# MN42_v2.net
KiCad netlist of a schematic drawn in EasyEDA Pro
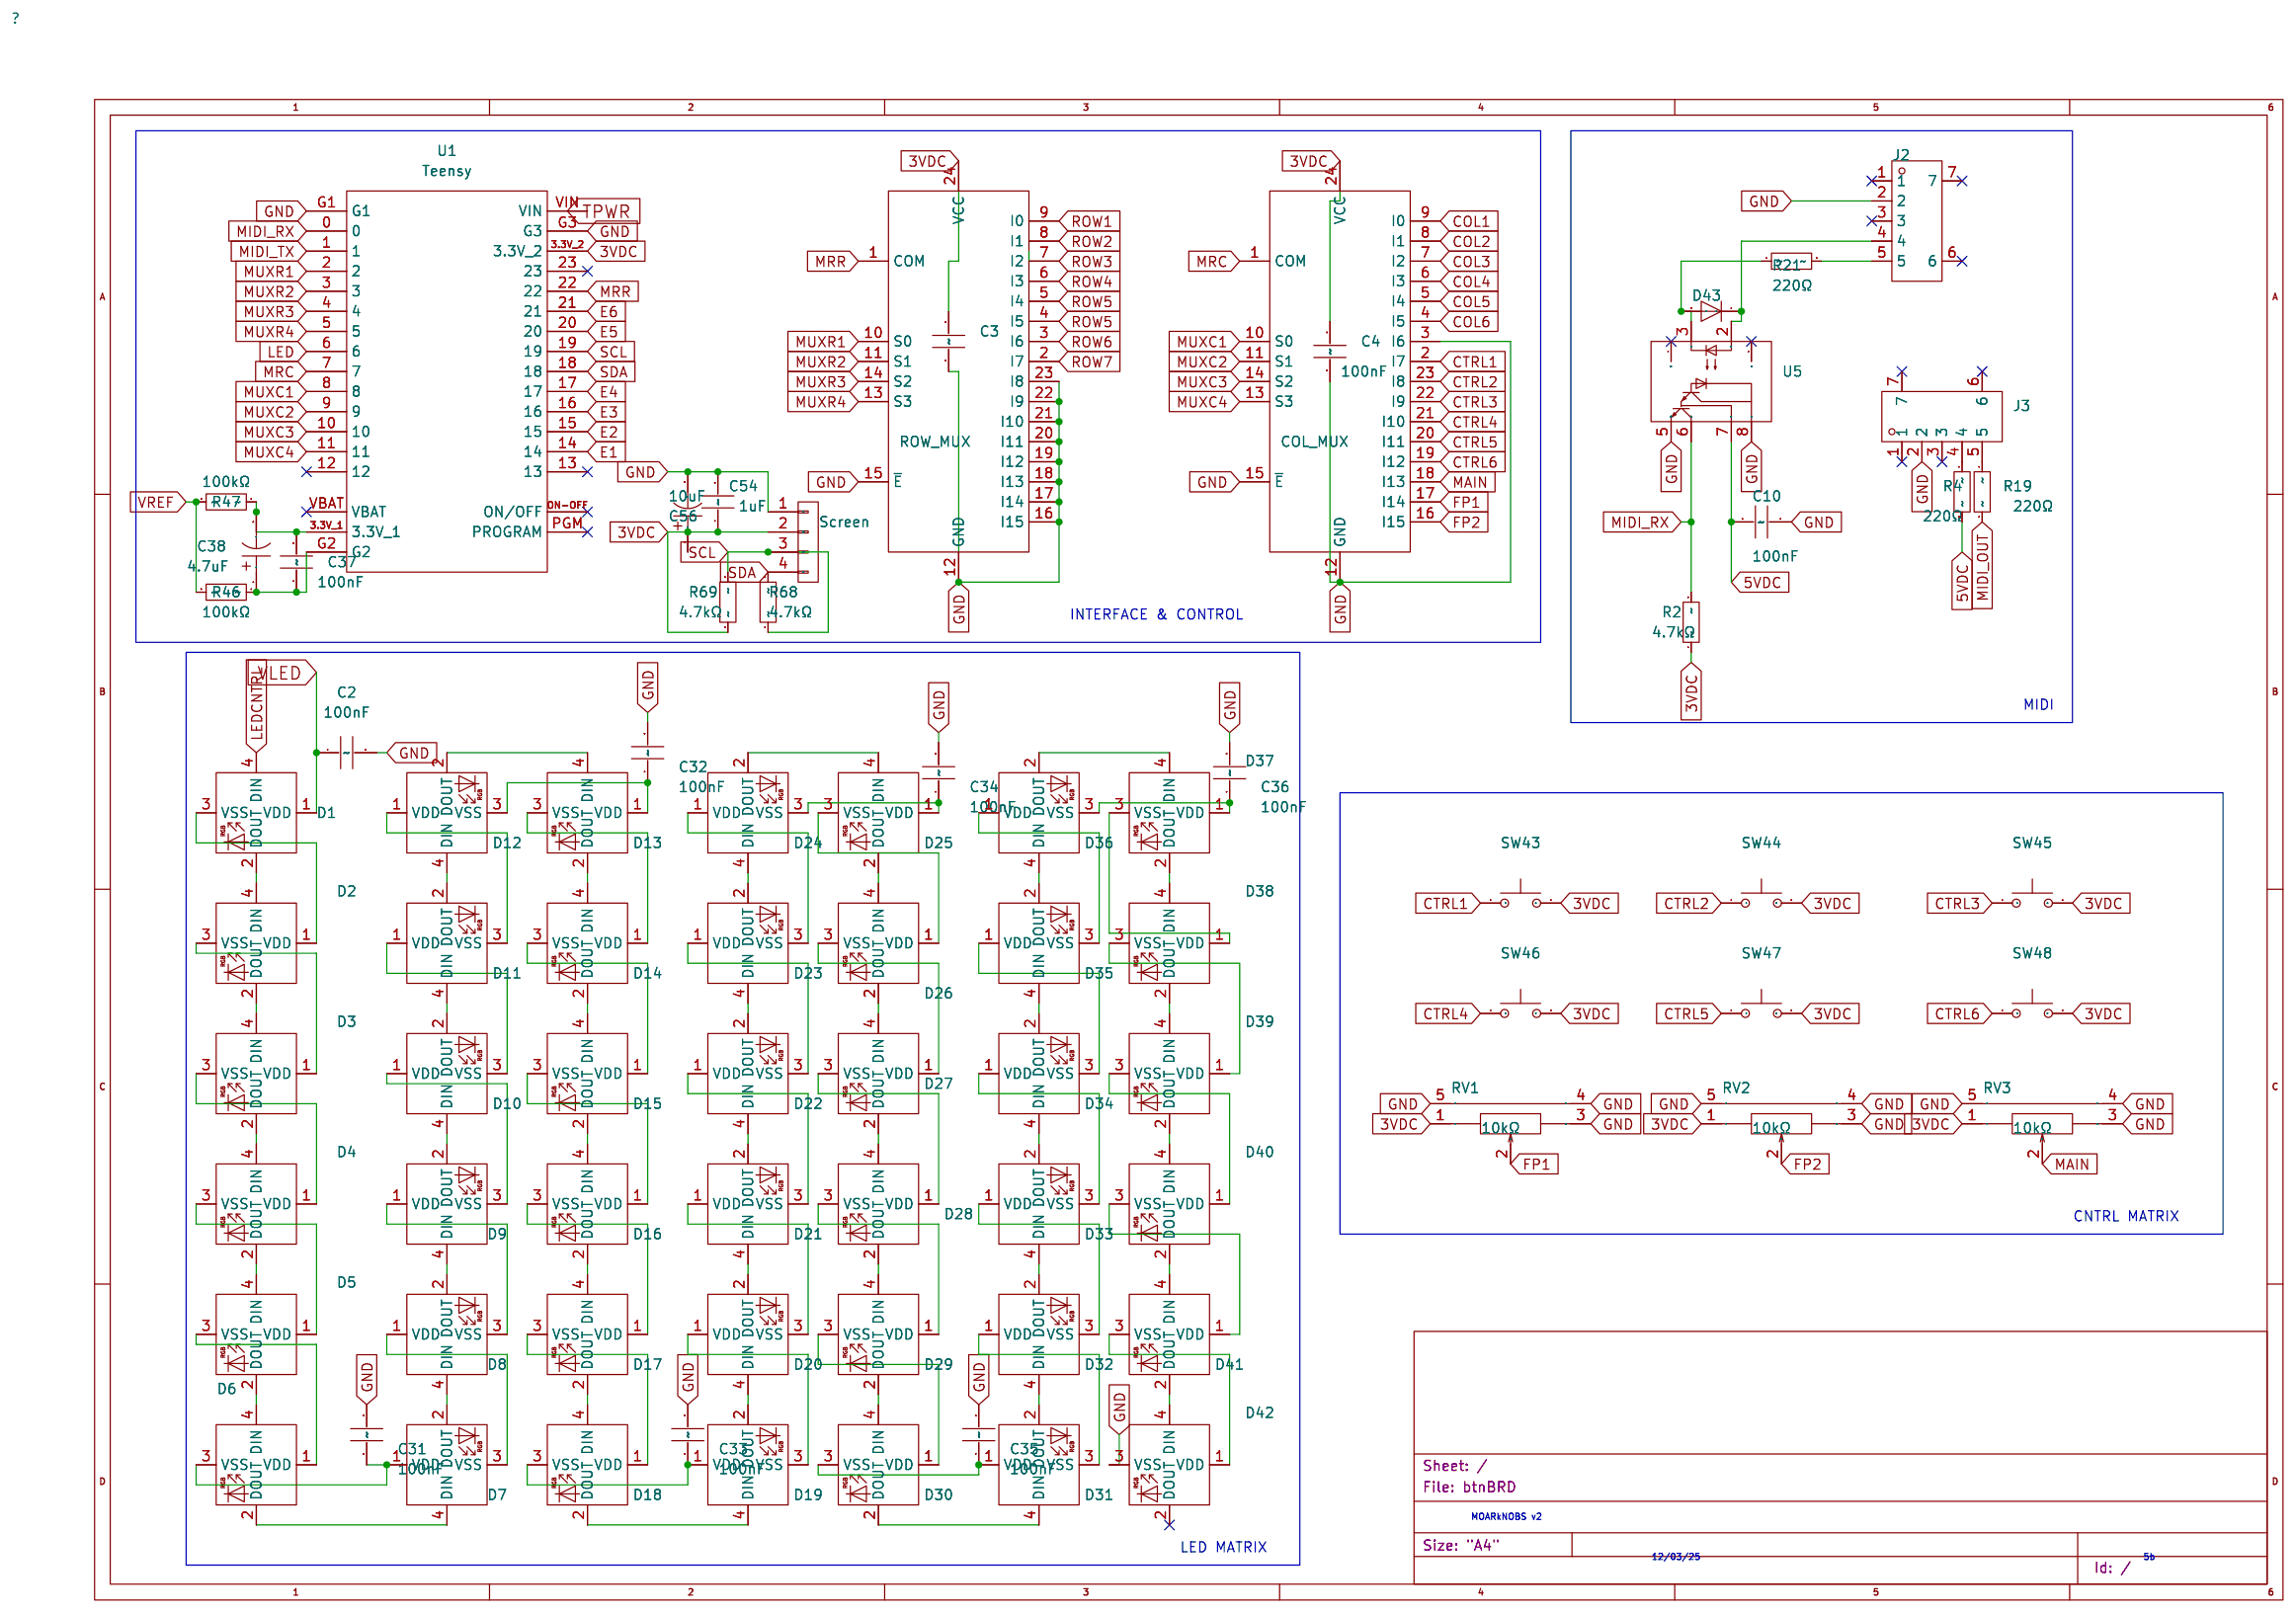
[diagram p0: btnBRD]
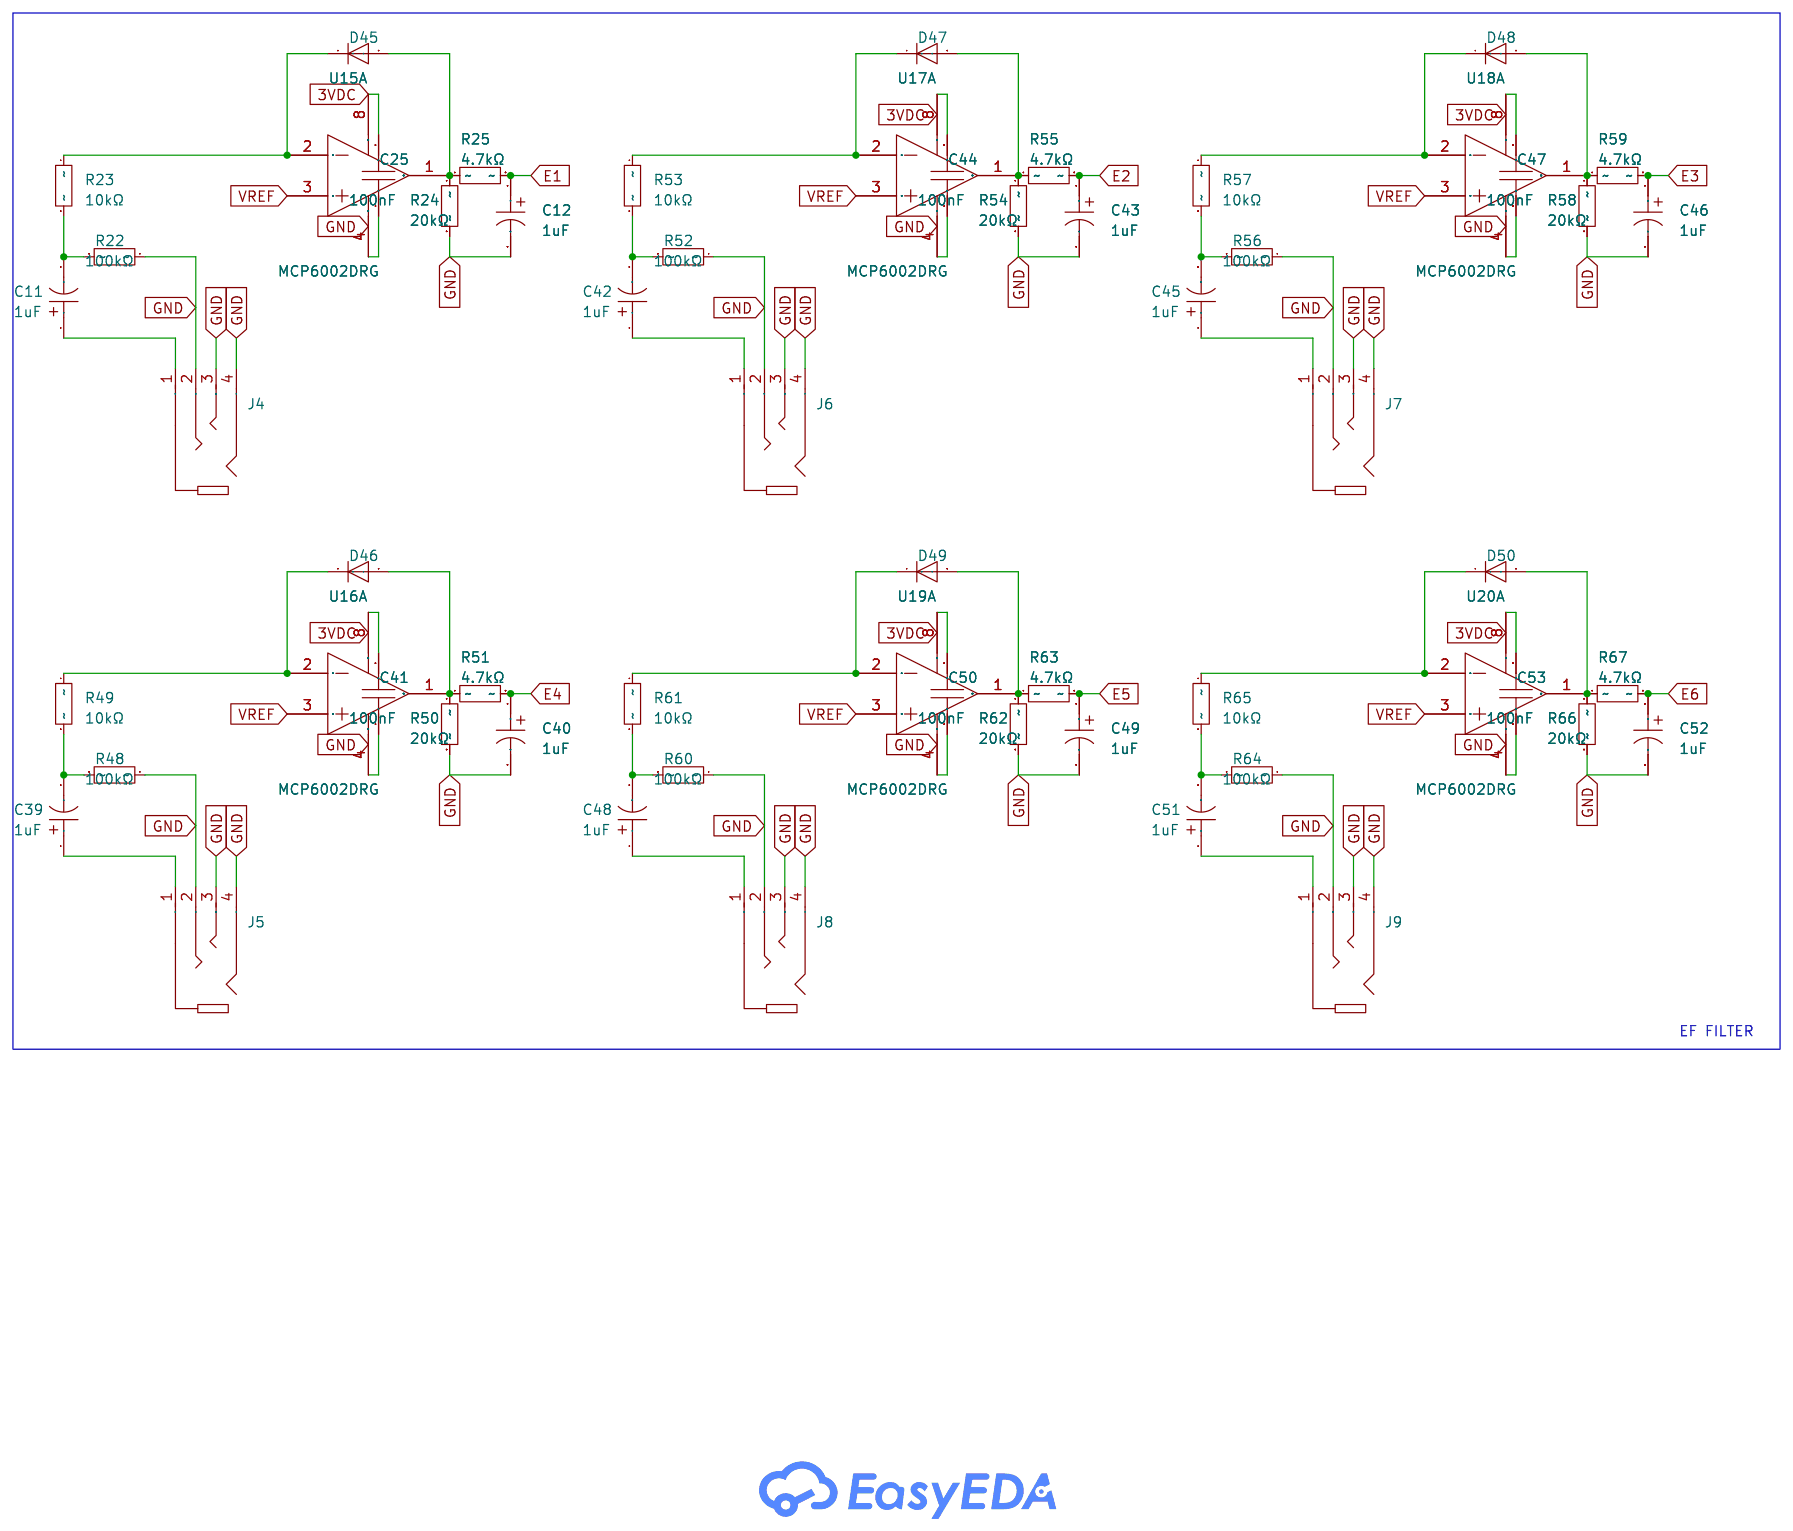
[diagram p1: P2]
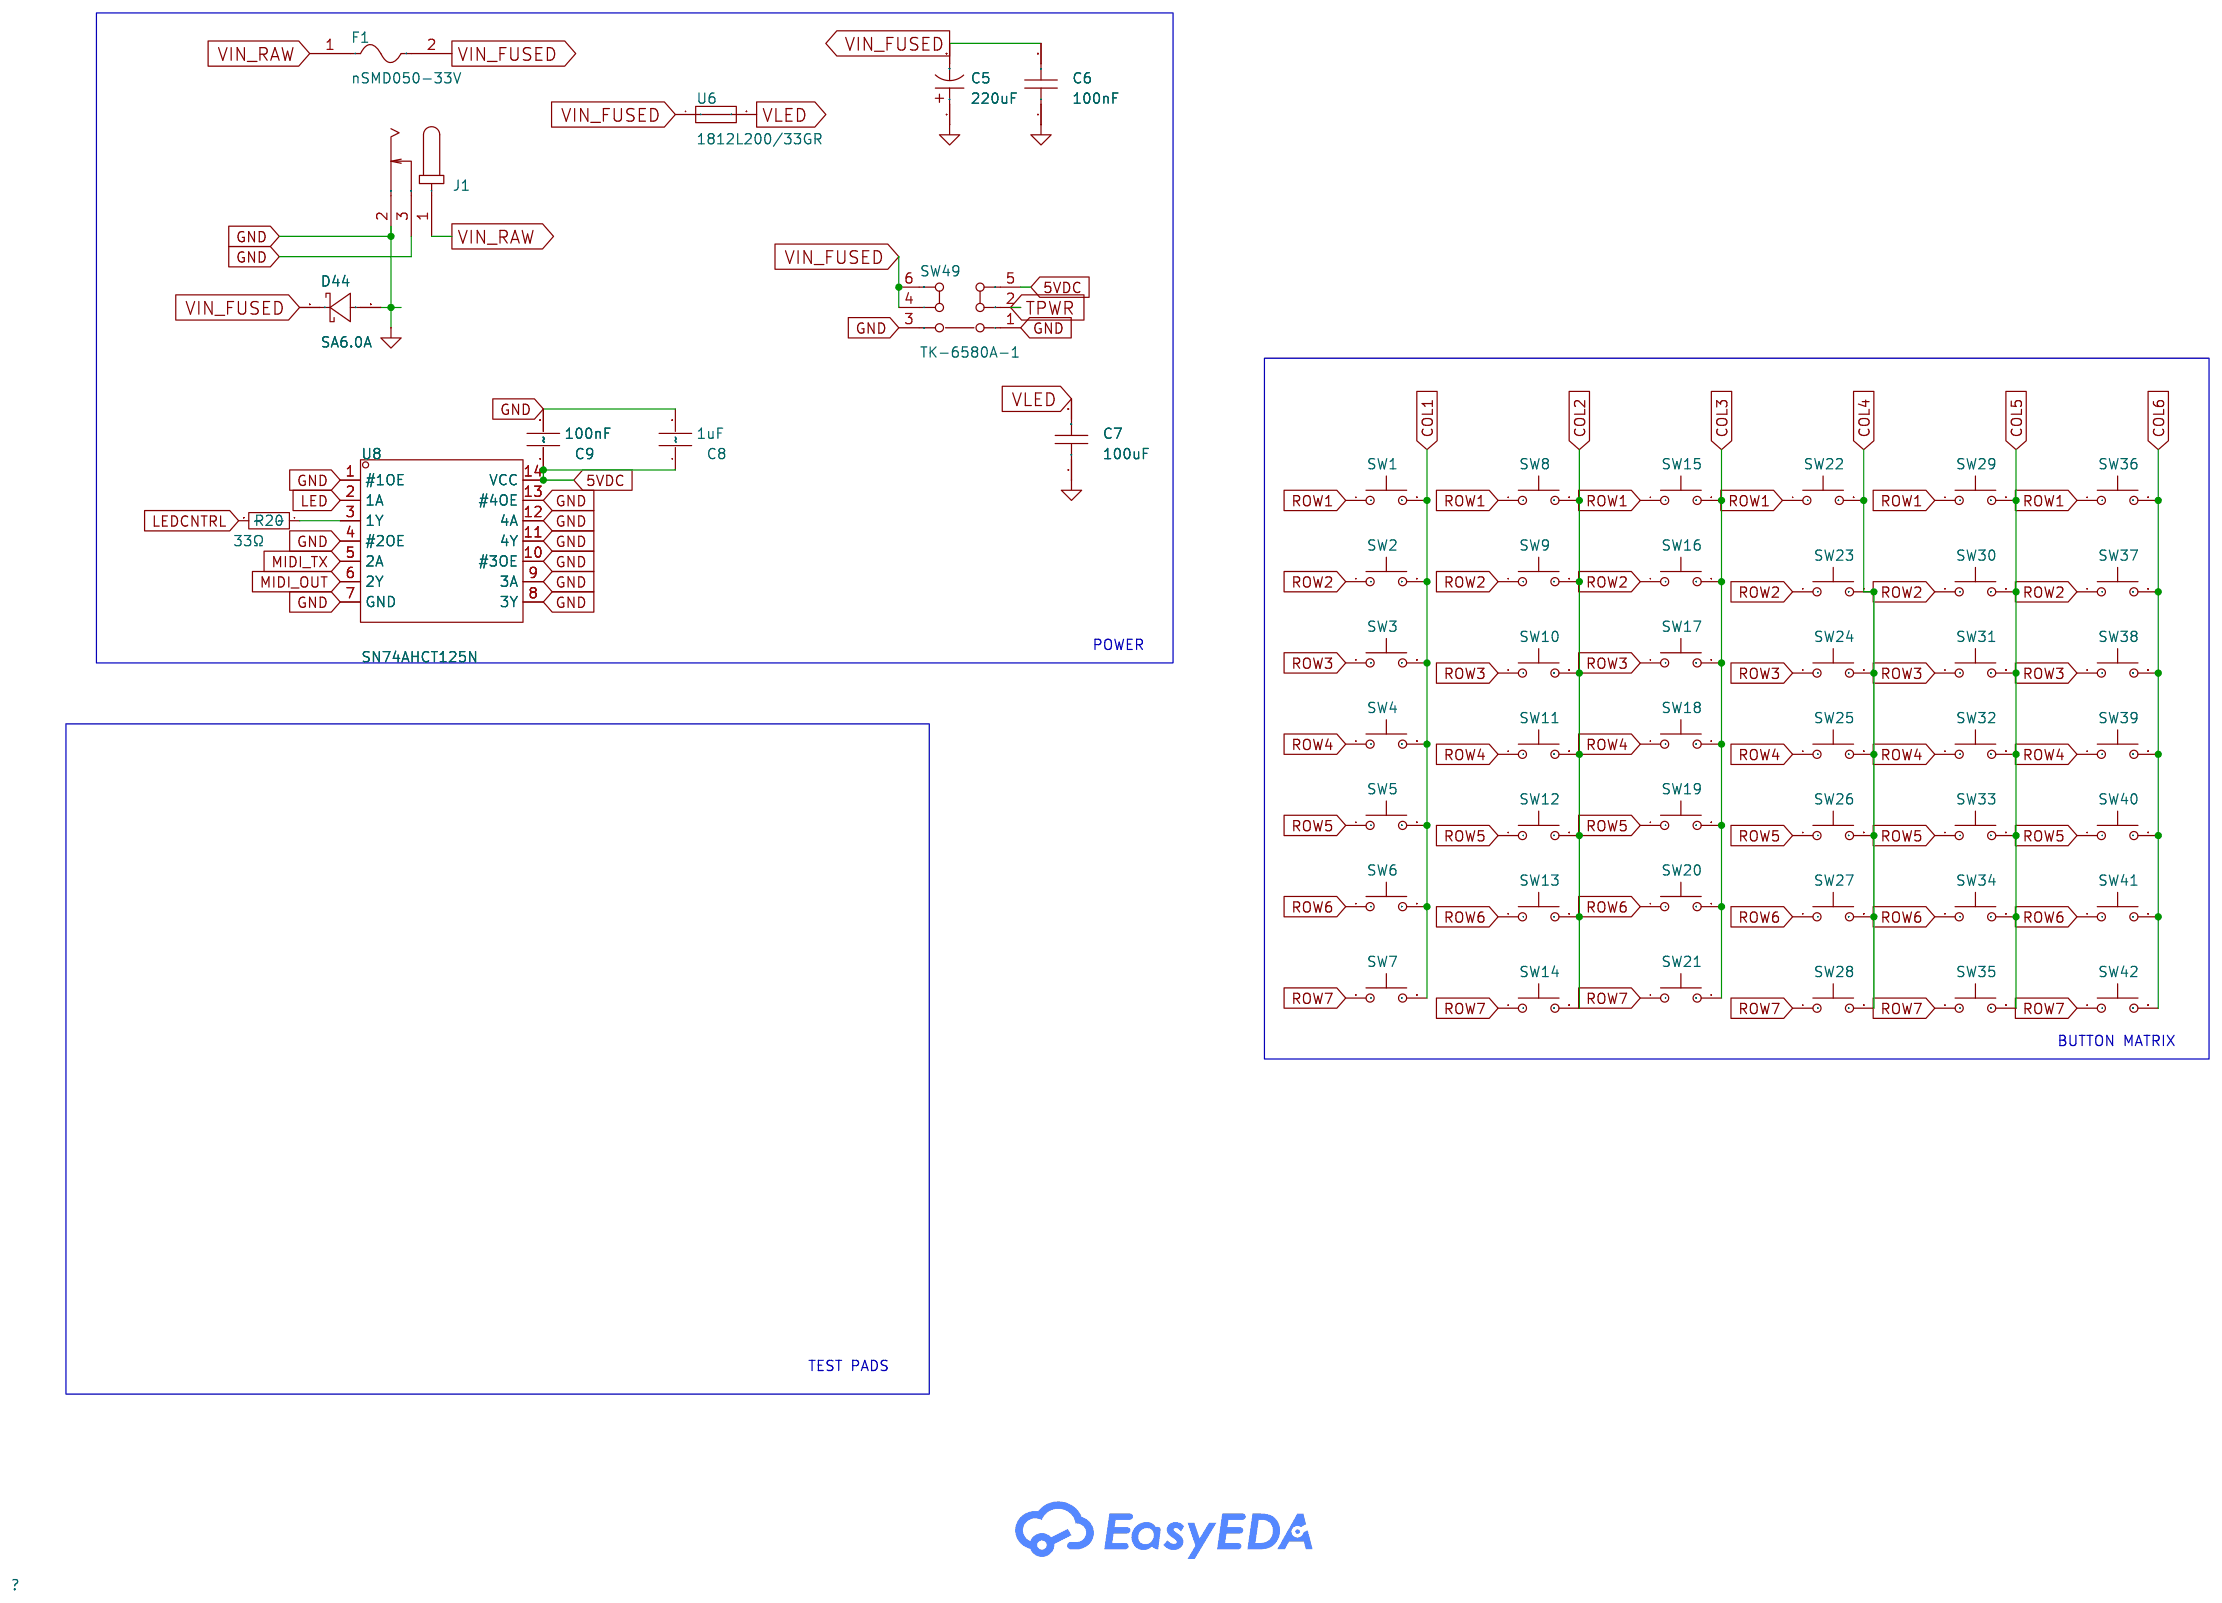
[diagram p2: P3]

(export (version "E")
  (design (tool "Eeschema 10.0.6"))
  (components
    (comp (ref "C2")
      (value "100nF")
      (footprint "easyedapro:Capacitor_THT:C_Disc_D3.4mm_W2.1mm_P2.50mm")
      (description "Capacitance:100nF Tolerance:±10% Tolerance:±10% Voltage Rating:63V Temperature Coefficient:-")
      (fields
        (field (name "Manufacturer Part") "CT4G-0805-2X1-63V-0.1μF-K")
        (field (name "Manufacturer") "TORCH(火炬)")
      )
      (libsource (lib "easyedapro") (part "Device_C"))
    )
    (comp (ref "C3")
      (value "100nF")
      (footprint "easyedapro:Capacitor_THT:C_Disc_D3.4mm_W2.1mm_P2.50mm")
      (description "Capacitance:100nF Tolerance:±10% Tolerance:±10% Voltage Rating:63V Temperature Coefficient:-")
      (fields
        (field (name "Manufacturer Part") "CT4G-0805-2X1-63V-0.1μF-K")
        (field (name "Manufacturer") "TORCH(火炬)")
      )
      (libsource (lib "easyedapro") (part "Device_C"))
    )
    (comp (ref "C4")
      (value "100nF")
      (footprint "easyedapro:Capacitor_THT:C_Disc_D3.4mm_W2.1mm_P2.50mm")
      (description "Capacitance:100nF Tolerance:±10% Tolerance:±10% Voltage Rating:63V Temperature Coefficient:-")
      (fields
        (field (name "Manufacturer Part") "CT4G-0805-2X1-63V-0.1μF-K")
        (field (name "Manufacturer") "TORCH(火炬)")
      )
      (libsource (lib "easyedapro") (part "Device_C"))
    )
    (comp (ref "C10")
      (value "100nF")
      (footprint "easyedapro:Capacitor_THT:C_Disc_D3.4mm_W2.1mm_P2.50mm")
      (description "Capacitance:100nF Tolerance:±10% Tolerance:±10% Voltage Rating:63V Temperature Coefficient:-")
      (fields
        (field (name "Manufacturer Part") "CT4G-0805-2X1-63V-0.1μF-K")
        (field (name "Manufacturer") "TORCH(火炬)")
      )
      (libsource (lib "easyedapro") (part "Device_C"))
    )
    (comp (ref "C31")
      (value "100nF")
      (footprint "easyedapro:Capacitor_THT:C_Disc_D3.4mm_W2.1mm_P2.50mm")
      (description "Capacitance:100nF Tolerance:±10% Tolerance:±10% Voltage Rating:63V Temperature Coefficient:-")
      (fields
        (field (name "Manufacturer Part") "CT4G-0805-2X1-63V-0.1μF-K")
        (field (name "Manufacturer") "TORCH(火炬)")
      )
      (libsource (lib "easyedapro") (part "Device_C"))
    )
    (comp (ref "C32")
      (value "100nF")
      (footprint "easyedapro:Capacitor_THT:C_Disc_D3.4mm_W2.1mm_P2.50mm")
      (description "Capacitance:100nF Tolerance:±10% Tolerance:±10% Voltage Rating:63V Temperature Coefficient:-")
      (fields
        (field (name "Manufacturer Part") "CT4G-0805-2X1-63V-0.1μF-K")
        (field (name "Manufacturer") "TORCH(火炬)")
      )
      (libsource (lib "easyedapro") (part "Device_C"))
    )
    (comp (ref "C33")
      (value "100nF")
      (footprint "easyedapro:Capacitor_THT:C_Disc_D3.4mm_W2.1mm_P2.50mm")
      (description "Capacitance:100nF Tolerance:±10% Tolerance:±10% Voltage Rating:63V Temperature Coefficient:-")
      (fields
        (field (name "Manufacturer Part") "CT4G-0805-2X1-63V-0.1μF-K")
        (field (name "Manufacturer") "TORCH(火炬)")
      )
      (libsource (lib "easyedapro") (part "Device_C"))
    )
    (comp (ref "C34")
      (value "100nF")
      (footprint "easyedapro:Capacitor_THT:C_Disc_D3.4mm_W2.1mm_P2.50mm")
      (description "Capacitance:100nF Tolerance:±10% Tolerance:±10% Voltage Rating:63V Temperature Coefficient:-")
      (fields
        (field (name "Manufacturer Part") "CT4G-0805-2X1-63V-0.1μF-K")
        (field (name "Manufacturer") "TORCH(火炬)")
      )
      (libsource (lib "easyedapro") (part "Device_C"))
    )
    (comp (ref "C35")
      (value "100nF")
      (footprint "easyedapro:Capacitor_THT:C_Disc_D3.4mm_W2.1mm_P2.50mm")
      (description "Capacitance:100nF Tolerance:±10% Tolerance:±10% Voltage Rating:63V Temperature Coefficient:-")
      (fields
        (field (name "Manufacturer Part") "CT4G-0805-2X1-63V-0.1μF-K")
        (field (name "Manufacturer") "TORCH(火炬)")
      )
      (libsource (lib "easyedapro") (part "Device_C"))
    )
    (comp (ref "C36")
      (value "100nF")
      (footprint "easyedapro:Capacitor_THT:C_Disc_D3.4mm_W2.1mm_P2.50mm")
      (description "Capacitance:100nF Tolerance:±10% Tolerance:±10% Voltage Rating:63V Temperature Coefficient:-")
      (fields
        (field (name "Manufacturer Part") "CT4G-0805-2X1-63V-0.1μF-K")
        (field (name "Manufacturer") "TORCH(火炬)")
      )
      (libsource (lib "easyedapro") (part "Device_C"))
    )
    (comp (ref "C37")
      (value "100nF")
      (footprint "easyedapro:Capacitor_THT:C_Disc_D3.4mm_W2.1mm_P2.50mm")
      (description "Capacitance:100nF Tolerance:±10% Tolerance:±10% Voltage Rating:63V Temperature Coefficient:-")
      (fields
        (field (name "Manufacturer Part") "CT4G-0805-2X1-63V-0.1μF-K")
        (field (name "Manufacturer") "TORCH(火炬)")
      )
      (libsource (lib "easyedapro") (part "Device_C"))
    )
    (comp (ref "C38")
      (value "4.7uF")
      (footprint "easyedapro:CAP-SMD_BD6.3-L6.6-W6.6-FD")
      (fields (field (name "Manufacturer Part") "189RV0019") (field (name "Manufacturer") "KNSCHA(科尼盛)"))
      (libsource (lib "easyedapro") (part "189RV0019"))
    )
    (comp (ref "C54")
      (value "1uF")
      (footprint "easyedapro:Capacitor_THT:C_Disc_D3.4mm_W2.1mm_P2.50mm")
      (description "Capacitance:100nF Tolerance:±10% Tolerance:±10% Voltage Rating:63V Temperature Coefficient:-")
      (fields
        (field (name "Manufacturer Part") "CT4G-0805-2X1-63V-0.1μF-K")
        (field (name "Manufacturer") "TORCH(火炬)")
      )
      (libsource (lib "easyedapro") (part "Device_C"))
    )
    (comp (ref "C56")
      (value "10uF")
      (footprint "easyedapro:CAP-SMD_BD6.3-L6.6-W6.6-FD")
      (fields (field (name "Manufacturer Part") "189RV0019") (field (name "Manufacturer") "KNSCHA(科尼盛)"))
      (libsource (lib "easyedapro") (part "189RV0019"))
    )
    (comp (ref "COL_MUX")
      (value "CD74HC4067M96")
      (footprint "easyedapro:Package_SO:SOIC-24W_7.5x15.4mm_P1.27mm")
      (fields (field (name "Manufacturer") "TI(德州仪器)"))
      (libsource (lib "easyedapro") (part "74xx_CD74HC4067M"))
    )
    (comp (ref "D1")
      (value "XL-5050RGBC-WS2812B")
      (footprint "easyedapro:LED_SMD:LED_WS2812B_PLCC4_5.0x5.0mm_P3.2mm")
      (fields (field (name "Manufacturer") "XINGLIGHT(成兴光)"))
      (libsource (lib "easyedapro") (part "LED_WS2812B"))
    )
    (comp (ref "D2")
      (value "XL-5050RGBC-WS2812B")
      (footprint "easyedapro:LED_SMD:LED_WS2812B_PLCC4_5.0x5.0mm_P3.2mm")
      (fields (field (name "Manufacturer") "XINGLIGHT(成兴光)"))
      (libsource (lib "easyedapro") (part "LED_WS2812B"))
    )
    (comp (ref "D3")
      (value "XL-5050RGBC-WS2812B")
      (footprint "easyedapro:LED_SMD:LED_WS2812B_PLCC4_5.0x5.0mm_P3.2mm")
      (fields (field (name "Manufacturer") "XINGLIGHT(成兴光)"))
      (libsource (lib "easyedapro") (part "LED_WS2812B"))
    )
    (comp (ref "D4")
      (value "XL-5050RGBC-WS2812B")
      (footprint "easyedapro:LED_SMD:LED_WS2812B_PLCC4_5.0x5.0mm_P3.2mm")
      (fields (field (name "Manufacturer") "XINGLIGHT(成兴光)"))
      (libsource (lib "easyedapro") (part "LED_WS2812B"))
    )
    (comp (ref "D5")
      (value "XL-5050RGBC-WS2812B")
      (footprint "easyedapro:LED_SMD:LED_WS2812B_PLCC4_5.0x5.0mm_P3.2mm")
      (fields (field (name "Manufacturer") "XINGLIGHT(成兴光)"))
      (libsource (lib "easyedapro") (part "LED_WS2812B"))
    )
    (comp (ref "D6")
      (value "XL-5050RGBC-WS2812B")
      (footprint "easyedapro:LED_SMD:LED_WS2812B_PLCC4_5.0x5.0mm_P3.2mm")
      (fields (field (name "Manufacturer") "XINGLIGHT(成兴光)"))
      (libsource (lib "easyedapro") (part "LED_WS2812B"))
    )
    (comp (ref "D7")
      (value "XL-5050RGBC-WS2812B")
      (footprint "easyedapro:LED_SMD:LED_WS2812B_PLCC4_5.0x5.0mm_P3.2mm")
      (fields (field (name "Manufacturer") "XINGLIGHT(成兴光)"))
      (libsource (lib "easyedapro") (part "LED_WS2812B"))
    )
    (comp (ref "D8")
      (value "XL-5050RGBC-WS2812B")
      (footprint "easyedapro:LED_SMD:LED_WS2812B_PLCC4_5.0x5.0mm_P3.2mm")
      (fields (field (name "Manufacturer") "XINGLIGHT(成兴光)"))
      (libsource (lib "easyedapro") (part "LED_WS2812B"))
    )
    (comp (ref "D9")
      (value "XL-5050RGBC-WS2812B")
      (footprint "easyedapro:LED_SMD:LED_WS2812B_PLCC4_5.0x5.0mm_P3.2mm")
      (fields (field (name "Manufacturer") "XINGLIGHT(成兴光)"))
      (libsource (lib "easyedapro") (part "LED_WS2812B"))
    )
    (comp (ref "D10")
      (value "XL-5050RGBC-WS2812B")
      (footprint "easyedapro:LED_SMD:LED_WS2812B_PLCC4_5.0x5.0mm_P3.2mm")
      (fields (field (name "Manufacturer") "XINGLIGHT(成兴光)"))
      (libsource (lib "easyedapro") (part "LED_WS2812B"))
    )
    (comp (ref "D11")
      (value "XL-5050RGBC-WS2812B")
      (footprint "easyedapro:LED_SMD:LED_WS2812B_PLCC4_5.0x5.0mm_P3.2mm")
      (fields (field (name "Manufacturer") "XINGLIGHT(成兴光)"))
      (libsource (lib "easyedapro") (part "LED_WS2812B"))
    )
    (comp (ref "D12")
      (value "XL-5050RGBC-WS2812B")
      (footprint "easyedapro:LED_SMD:LED_WS2812B_PLCC4_5.0x5.0mm_P3.2mm")
      (fields (field (name "Manufacturer") "XINGLIGHT(成兴光)"))
      (libsource (lib "easyedapro") (part "LED_WS2812B"))
    )
    (comp (ref "D13")
      (value "XL-5050RGBC-WS2812B")
      (footprint "easyedapro:LED_SMD:LED_WS2812B_PLCC4_5.0x5.0mm_P3.2mm")
      (fields (field (name "Manufacturer") "XINGLIGHT(成兴光)"))
      (libsource (lib "easyedapro") (part "LED_WS2812B"))
    )
    (comp (ref "D14")
      (value "XL-5050RGBC-WS2812B")
      (footprint "easyedapro:LED_SMD:LED_WS2812B_PLCC4_5.0x5.0mm_P3.2mm")
      (fields (field (name "Manufacturer") "XINGLIGHT(成兴光)"))
      (libsource (lib "easyedapro") (part "LED_WS2812B"))
    )
    (comp (ref "D15")
      (value "XL-5050RGBC-WS2812B")
      (footprint "easyedapro:LED_SMD:LED_WS2812B_PLCC4_5.0x5.0mm_P3.2mm")
      (fields (field (name "Manufacturer") "XINGLIGHT(成兴光)"))
      (libsource (lib "easyedapro") (part "LED_WS2812B"))
    )
    (comp (ref "D16")
      (value "XL-5050RGBC-WS2812B")
      (footprint "easyedapro:LED_SMD:LED_WS2812B_PLCC4_5.0x5.0mm_P3.2mm")
      (fields (field (name "Manufacturer") "XINGLIGHT(成兴光)"))
      (libsource (lib "easyedapro") (part "LED_WS2812B"))
    )
    (comp (ref "D17")
      (value "XL-5050RGBC-WS2812B")
      (footprint "easyedapro:LED_SMD:LED_WS2812B_PLCC4_5.0x5.0mm_P3.2mm")
      (fields (field (name "Manufacturer") "XINGLIGHT(成兴光)"))
      (libsource (lib "easyedapro") (part "LED_WS2812B"))
    )
    (comp (ref "D18")
      (value "XL-5050RGBC-WS2812B")
      (footprint "easyedapro:LED_SMD:LED_WS2812B_PLCC4_5.0x5.0mm_P3.2mm")
      (fields (field (name "Manufacturer") "XINGLIGHT(成兴光)"))
      (libsource (lib "easyedapro") (part "LED_WS2812B"))
    )
    (comp (ref "D19")
      (value "XL-5050RGBC-WS2812B")
      (footprint "easyedapro:LED_SMD:LED_WS2812B_PLCC4_5.0x5.0mm_P3.2mm")
      (fields (field (name "Manufacturer") "XINGLIGHT(成兴光)"))
      (libsource (lib "easyedapro") (part "LED_WS2812B"))
    )
    (comp (ref "D20")
      (value "XL-5050RGBC-WS2812B")
      (footprint "easyedapro:LED_SMD:LED_WS2812B_PLCC4_5.0x5.0mm_P3.2mm")
      (fields (field (name "Manufacturer") "XINGLIGHT(成兴光)"))
      (libsource (lib "easyedapro") (part "LED_WS2812B"))
    )
    (comp (ref "D21")
      (value "XL-5050RGBC-WS2812B")
      (footprint "easyedapro:LED_SMD:LED_WS2812B_PLCC4_5.0x5.0mm_P3.2mm")
      (fields (field (name "Manufacturer") "XINGLIGHT(成兴光)"))
      (libsource (lib "easyedapro") (part "LED_WS2812B"))
    )
    (comp (ref "D22")
      (value "XL-5050RGBC-WS2812B")
      (footprint "easyedapro:LED_SMD:LED_WS2812B_PLCC4_5.0x5.0mm_P3.2mm")
      (fields (field (name "Manufacturer") "XINGLIGHT(成兴光)"))
      (libsource (lib "easyedapro") (part "LED_WS2812B"))
    )
    (comp (ref "D23")
      (value "XL-5050RGBC-WS2812B")
      (footprint "easyedapro:LED_SMD:LED_WS2812B_PLCC4_5.0x5.0mm_P3.2mm")
      (fields (field (name "Manufacturer") "XINGLIGHT(成兴光)"))
      (libsource (lib "easyedapro") (part "LED_WS2812B"))
    )
    (comp (ref "D24")
      (value "XL-5050RGBC-WS2812B")
      (footprint "easyedapro:LED_SMD:LED_WS2812B_PLCC4_5.0x5.0mm_P3.2mm")
      (fields (field (name "Manufacturer") "XINGLIGHT(成兴光)"))
      (libsource (lib "easyedapro") (part "LED_WS2812B"))
    )
    (comp (ref "D25")
      (value "XL-5050RGBC-WS2812B")
      (footprint "easyedapro:LED_SMD:LED_WS2812B_PLCC4_5.0x5.0mm_P3.2mm")
      (fields (field (name "Manufacturer") "XINGLIGHT(成兴光)"))
      (libsource (lib "easyedapro") (part "LED_WS2812B"))
    )
    (comp (ref "D26")
      (value "XL-5050RGBC-WS2812B")
      (footprint "easyedapro:LED_SMD:LED_WS2812B_PLCC4_5.0x5.0mm_P3.2mm")
      (fields (field (name "Manufacturer") "XINGLIGHT(成兴光)"))
      (libsource (lib "easyedapro") (part "LED_WS2812B"))
    )
    (comp (ref "D27")
      (value "XL-5050RGBC-WS2812B")
      (footprint "easyedapro:LED_SMD:LED_WS2812B_PLCC4_5.0x5.0mm_P3.2mm")
      (fields (field (name "Manufacturer") "XINGLIGHT(成兴光)"))
      (libsource (lib "easyedapro") (part "LED_WS2812B"))
    )
    (comp (ref "D28")
      (value "XL-5050RGBC-WS2812B")
      (footprint "easyedapro:LED_SMD:LED_WS2812B_PLCC4_5.0x5.0mm_P3.2mm")
      (fields (field (name "Manufacturer") "XINGLIGHT(成兴光)"))
      (libsource (lib "easyedapro") (part "LED_WS2812B"))
    )
    (comp (ref "D29")
      (value "XL-5050RGBC-WS2812B")
      (footprint "easyedapro:LED_SMD:LED_WS2812B_PLCC4_5.0x5.0mm_P3.2mm")
      (fields (field (name "Manufacturer") "XINGLIGHT(成兴光)"))
      (libsource (lib "easyedapro") (part "LED_WS2812B"))
    )
    (comp (ref "D30")
      (value "XL-5050RGBC-WS2812B")
      (footprint "easyedapro:LED_SMD:LED_WS2812B_PLCC4_5.0x5.0mm_P3.2mm")
      (fields (field (name "Manufacturer") "XINGLIGHT(成兴光)"))
      (libsource (lib "easyedapro") (part "LED_WS2812B"))
    )
    (comp (ref "D31")
      (value "XL-5050RGBC-WS2812B")
      (footprint "easyedapro:LED_SMD:LED_WS2812B_PLCC4_5.0x5.0mm_P3.2mm")
      (fields (field (name "Manufacturer") "XINGLIGHT(成兴光)"))
      (libsource (lib "easyedapro") (part "LED_WS2812B"))
    )
    (comp (ref "D32")
      (value "XL-5050RGBC-WS2812B")
      (footprint "easyedapro:LED_SMD:LED_WS2812B_PLCC4_5.0x5.0mm_P3.2mm")
      (fields (field (name "Manufacturer") "XINGLIGHT(成兴光)"))
      (libsource (lib "easyedapro") (part "LED_WS2812B"))
    )
    (comp (ref "D33")
      (value "XL-5050RGBC-WS2812B")
      (footprint "easyedapro:LED_SMD:LED_WS2812B_PLCC4_5.0x5.0mm_P3.2mm")
      (fields (field (name "Manufacturer") "XINGLIGHT(成兴光)"))
      (libsource (lib "easyedapro") (part "LED_WS2812B"))
    )
    (comp (ref "D34")
      (value "XL-5050RGBC-WS2812B")
      (footprint "easyedapro:LED_SMD:LED_WS2812B_PLCC4_5.0x5.0mm_P3.2mm")
      (fields (field (name "Manufacturer") "XINGLIGHT(成兴光)"))
      (libsource (lib "easyedapro") (part "LED_WS2812B"))
    )
    (comp (ref "D35")
      (value "XL-5050RGBC-WS2812B")
      (footprint "easyedapro:LED_SMD:LED_WS2812B_PLCC4_5.0x5.0mm_P3.2mm")
      (fields (field (name "Manufacturer") "XINGLIGHT(成兴光)"))
      (libsource (lib "easyedapro") (part "LED_WS2812B"))
    )
    (comp (ref "D36")
      (value "XL-5050RGBC-WS2812B")
      (footprint "easyedapro:LED_SMD:LED_WS2812B_PLCC4_5.0x5.0mm_P3.2mm")
      (fields (field (name "Manufacturer") "XINGLIGHT(成兴光)"))
      (libsource (lib "easyedapro") (part "LED_WS2812B"))
    )
    (comp (ref "D37")
      (value "XL-5050RGBC-WS2812B")
      (footprint "easyedapro:LED_SMD:LED_WS2812B_PLCC4_5.0x5.0mm_P3.2mm")
      (fields (field (name "Manufacturer") "XINGLIGHT(成兴光)"))
      (libsource (lib "easyedapro") (part "LED_WS2812B"))
    )
    (comp (ref "D38")
      (value "XL-5050RGBC-WS2812B")
      (footprint "easyedapro:LED_SMD:LED_WS2812B_PLCC4_5.0x5.0mm_P3.2mm")
      (fields (field (name "Manufacturer") "XINGLIGHT(成兴光)"))
      (libsource (lib "easyedapro") (part "LED_WS2812B"))
    )
    (comp (ref "D39")
      (value "XL-5050RGBC-WS2812B")
      (footprint "easyedapro:LED_SMD:LED_WS2812B_PLCC4_5.0x5.0mm_P3.2mm")
      (fields (field (name "Manufacturer") "XINGLIGHT(成兴光)"))
      (libsource (lib "easyedapro") (part "LED_WS2812B"))
    )
    (comp (ref "D40")
      (value "XL-5050RGBC-WS2812B")
      (footprint "easyedapro:LED_SMD:LED_WS2812B_PLCC4_5.0x5.0mm_P3.2mm")
      (fields (field (name "Manufacturer") "XINGLIGHT(成兴光)"))
      (libsource (lib "easyedapro") (part "LED_WS2812B"))
    )
    (comp (ref "D41")
      (value "XL-5050RGBC-WS2812B")
      (footprint "easyedapro:LED_SMD:LED_WS2812B_PLCC4_5.0x5.0mm_P3.2mm")
      (fields (field (name "Manufacturer") "XINGLIGHT(成兴光)"))
      (libsource (lib "easyedapro") (part "LED_WS2812B"))
    )
    (comp (ref "D42")
      (value "XL-5050RGBC-WS2812B")
      (footprint "easyedapro:LED_SMD:LED_WS2812B_PLCC4_5.0x5.0mm_P3.2mm")
      (fields (field (name "Manufacturer") "XINGLIGHT(成兴光)"))
      (libsource (lib "easyedapro") (part "LED_WS2812B"))
    )
    (comp (ref "D43")
      (value "1N4148PF")
      (footprint "easyedapro:Diode_THT:D_DO-35_SOD27_P7.62mm_Horizontal")
      (fields (field (name "Manufacturer") "ST(先科)"))
      (libsource (lib "easyedapro") (part "Diode_1N4148"))
    )
    (comp (ref "J2")
      (value "DIN-504B-M10")
      (footprint "easyedapro:CONN-TH_DIN-504B-M10")
      (fields (field (name "Manufacturer") "HOOYA(皓宇电子)"))
      (libsource (lib "easyedapro") (part "DIN-504B-M10"))
    )
    (comp (ref "J3")
      (value "DIN-504B-M10")
      (footprint "easyedapro:CONN-TH_DIN-504B-M10")
      (fields (field (name "Manufacturer") "HOOYA(皓宇电子)"))
      (libsource (lib "easyedapro") (part "DIN-504B-M10"))
    )
    (comp (ref "R2")
      (value "4.7kΩ")
      (footprint "easyedapro:Resistor_THT:R_Axial_DIN0204_L3.6mm_D1.6mm_P2.54mm_Vertical")
      (fields
        (field (name "Manufacturer Part") "RN 1/8W 4K7 F T/B A1")
        (field (name "Manufacturer") "Tyohm(幸亚电阻)")
      )
      (libsource (lib "easyedapro") (part "Device_R"))
    )
    (comp (ref "R4")
      (value "220Ω")
      (footprint "easyedapro:Resistor_THT:R_Axial_DIN0204_L3.6mm_D1.6mm_P2.54mm_Vertical")
      (fields
        (field (name "Manufacturer Part") "RN 1/8W 220R F T/B A1")
        (field (name "Manufacturer") "Tyohm(幸亚电阻)")
      )
      (libsource (lib "easyedapro") (part "Device_R"))
    )
    (comp (ref "R19")
      (value "220Ω")
      (footprint "easyedapro:Resistor_THT:R_Axial_DIN0204_L3.6mm_D1.6mm_P2.54mm_Vertical")
      (fields
        (field (name "Manufacturer Part") "RN 1/8W 220R F T/B A1")
        (field (name "Manufacturer") "Tyohm(幸亚电阻)")
      )
      (libsource (lib "easyedapro") (part "Device_R"))
    )
    (comp (ref "R21")
      (value "220Ω")
      (footprint "easyedapro:Resistor_THT:R_Axial_DIN0204_L3.6mm_D1.6mm_P2.54mm_Vertical")
      (fields
        (field (name "Manufacturer Part") "RN 1/8W 220R F T/B A1")
        (field (name "Manufacturer") "Tyohm(幸亚电阻)")
      )
      (libsource (lib "easyedapro") (part "Device_R"))
    )
    (comp (ref "R46")
      (value "100kΩ")
      (footprint "easyedapro:Resistor_THT:R_Axial_DIN0204_L3.6mm_D1.6mm_P2.54mm_Vertical")
      (fields
        (field (name "Manufacturer Part") "RN1/8W10KFT/BA1")
        (field (name "Manufacturer") "Tyohm(幸亚电阻)")
      )
      (libsource (lib "easyedapro") (part "Device_R"))
    )
    (comp (ref "R47")
      (value "100kΩ")
      (footprint "easyedapro:Resistor_THT:R_Axial_DIN0204_L3.6mm_D1.6mm_P2.54mm_Vertical")
      (fields
        (field (name "Manufacturer Part") "RN1/8W10KFT/BA1")
        (field (name "Manufacturer") "Tyohm(幸亚电阻)")
      )
      (libsource (lib "easyedapro") (part "Device_R"))
    )
    (comp (ref "R68")
      (value "4.7kΩ")
      (footprint "easyedapro:Resistor_THT:R_Axial_DIN0204_L3.6mm_D1.6mm_P2.54mm_Vertical")
      (fields
        (field (name "Manufacturer Part") "RN 1/8W 4K7 F T/B A1")
        (field (name "Manufacturer") "Tyohm(幸亚电阻)")
      )
      (libsource (lib "easyedapro") (part "Device_R"))
    )
    (comp (ref "R69")
      (value "4.7kΩ")
      (footprint "easyedapro:Resistor_THT:R_Axial_DIN0204_L3.6mm_D1.6mm_P2.54mm_Vertical")
      (fields
        (field (name "Manufacturer Part") "RN 1/8W 4K7 F T/B A1")
        (field (name "Manufacturer") "Tyohm(幸亚电阻)")
      )
      (libsource (lib "easyedapro") (part "Device_R"))
    )
    (comp (ref "ROW_MUX")
      (value "CD74HC4067M96")
      (footprint "easyedapro:Package_SO:SOIC-24W_7.5x15.4mm_P1.27mm")
      (fields (field (name "Manufacturer") "TI(德州仪器)"))
      (libsource (lib "easyedapro") (part "74xx_CD74HC4067M"))
    )
    (comp (ref "RV1")
      (value "10kΩ")
      (footprint "easyedapro:RES-ADJ-TH_RK09K1130A5R")
      (description "Resistance: Tolerance:±20% Tolerance:±20%")
      (fields
        (field (name "Manufacturer Part") "RK09K1130A5R")
        (field (name "Manufacturer") "ALPSALPINE(阿尔卑斯阿尔派)")
      )
      (libsource (lib "easyedapro") (part "RK09K1130A5R"))
    )
    (comp (ref "RV2")
      (value "10kΩ")
      (footprint "easyedapro:RES-ADJ-TH_RK09K1130A5R")
      (description "Resistance: Tolerance:±20% Tolerance:±20%")
      (fields
        (field (name "Manufacturer Part") "RK09K1130A5R")
        (field (name "Manufacturer") "ALPSALPINE(阿尔卑斯阿尔派)")
      )
      (libsource (lib "easyedapro") (part "RK09K1130A5R"))
    )
    (comp (ref "RV3")
      (value "10kΩ")
      (footprint "easyedapro:RES-ADJ-TH_RK09K1130A5R")
      (description "Resistance: Tolerance:±20% Tolerance:±20%")
      (fields
        (field (name "Manufacturer Part") "RK09K1130A5R")
        (field (name "Manufacturer") "ALPSALPINE(阿尔卑斯阿尔派)")
      )
      (libsource (lib "easyedapro") (part "RK09K1130A5R"))
    )
    (comp (ref "Screen")
      (value "HS96L03W2C03")
      (footprint "easyedapro:Connector_JST:JST_EH_S4B-EH_1x04_P2.50mm_Horizontal")
      (fields (field (name "Manufacturer") "HS(汉昇)"))
      (libsource (lib "easyedapro") (part "Connector_Generic_Conn_01x04"))
    )
    (comp (ref "SW43")
      (value "HX B3F-4055-Y")
      (footprint "easyedapro:Button_Switch_SMD:SW_SPST_PTS645")
      (fields (field (name "Manufacturer") "hanxia(韩下)"))
      (libsource (lib "easyedapro") (part "Switch_SW_Push"))
    )
    (comp (ref "SW44")
      (value "HX B3F-4055-Y")
      (footprint "easyedapro:Button_Switch_SMD:SW_SPST_PTS645")
      (fields (field (name "Manufacturer") "hanxia(韩下)"))
      (libsource (lib "easyedapro") (part "Switch_SW_Push"))
    )
    (comp (ref "SW45")
      (value "HX B3F-4055-Y")
      (footprint "easyedapro:Button_Switch_SMD:SW_SPST_PTS645")
      (fields (field (name "Manufacturer") "hanxia(韩下)"))
      (libsource (lib "easyedapro") (part "Switch_SW_Push"))
    )
    (comp (ref "SW46")
      (value "HX B3F-4055-Y")
      (footprint "easyedapro:Button_Switch_SMD:SW_SPST_PTS645")
      (fields (field (name "Manufacturer") "hanxia(韩下)"))
      (libsource (lib "easyedapro") (part "Switch_SW_Push"))
    )
    (comp (ref "SW47")
      (value "HX B3F-4055-Y")
      (footprint "easyedapro:Button_Switch_SMD:SW_SPST_PTS645")
      (fields (field (name "Manufacturer") "hanxia(韩下)"))
      (libsource (lib "easyedapro") (part "Switch_SW_Push"))
    )
    (comp (ref "SW48")
      (value "HX B3F-4055-Y")
      (footprint "easyedapro:Button_Switch_SMD:SW_SPST_PTS645")
      (fields (field (name "Manufacturer") "hanxia(韩下)"))
      (libsource (lib "easyedapro") (part "Switch_SW_Push"))
    )
    (comp (ref "U1")
      (value "Teensy")
      (footprint "easyedapro:teensy 4.0:MODULE_DEV-15583")
      (libsource (lib "easyedapro") (part "teensy40_DEV-15583"))
    )
    (comp (ref "U5")
      (value "6N138")
      (footprint "easyedapro:Package_DIP:DIP-8_W7.62mm")
      (fields (field (name "Manufacturer") "ISOCOM(英国安数光)"))
      (libsource (lib "easyedapro") (part "Isolator_6N138"))
    )
    (comp (ref "C11")
      (value "1uF")
      (footprint "easyedapro:CAP-SMD_BD6.3-L6.6-W6.6-FD")
      (fields (field (name "Manufacturer Part") "189RV0019") (field (name "Manufacturer") "KNSCHA(科尼盛)"))
      (libsource (lib "easyedapro") (part "189RV0019"))
    )
    (comp (ref "C12")
      (value "1uF")
      (footprint "easyedapro:CAP-SMD_BD6.3-L6.6-W6.6-FD")
      (fields (field (name "Manufacturer Part") "189RV0019") (field (name "Manufacturer") "KNSCHA(科尼盛)"))
      (libsource (lib "easyedapro") (part "189RV0019"))
    )
    (comp (ref "C25")
      (value "100nF")
      (footprint "easyedapro:CAP-TH_L5.0-W2.5-P5.00-D1.0")
      (fields
        (field (name "Manufacturer Part") "CC1H104MC1FD3F6C10MF")
        (field (name "Manufacturer") "Dersonic(德尔创)")
      )
      (libsource (lib "easyedapro") (part "CC1H104MC1FD3F6C10MF"))
    )
    (comp (ref "C39")
      (value "1uF")
      (footprint "easyedapro:CAP-SMD_BD6.3-L6.6-W6.6-FD")
      (fields (field (name "Manufacturer Part") "189RV0019") (field (name "Manufacturer") "KNSCHA(科尼盛)"))
      (libsource (lib "easyedapro") (part "189RV0019"))
    )
    (comp (ref "C40")
      (value "1uF")
      (footprint "easyedapro:CAP-SMD_BD6.3-L6.6-W6.6-FD")
      (fields (field (name "Manufacturer Part") "189RV0019") (field (name "Manufacturer") "KNSCHA(科尼盛)"))
      (libsource (lib "easyedapro") (part "189RV0019"))
    )
    (comp (ref "C41")
      (value "100nF")
      (footprint "easyedapro:CAP-TH_L5.0-W2.5-P5.00-D1.0")
      (fields
        (field (name "Manufacturer Part") "CC1H104MC1FD3F6C10MF")
        (field (name "Manufacturer") "Dersonic(德尔创)")
      )
      (libsource (lib "easyedapro") (part "CC1H104MC1FD3F6C10MF"))
    )
    (comp (ref "C42")
      (value "1uF")
      (footprint "easyedapro:CAP-SMD_BD6.3-L6.6-W6.6-FD")
      (fields (field (name "Manufacturer Part") "189RV0019") (field (name "Manufacturer") "KNSCHA(科尼盛)"))
      (libsource (lib "easyedapro") (part "189RV0019"))
    )
    (comp (ref "C43")
      (value "1uF")
      (footprint "easyedapro:CAP-SMD_BD6.3-L6.6-W6.6-FD")
      (fields (field (name "Manufacturer Part") "189RV0019") (field (name "Manufacturer") "KNSCHA(科尼盛)"))
      (libsource (lib "easyedapro") (part "189RV0019"))
    )
    (comp (ref "C44")
      (value "100nF")
      (footprint "easyedapro:CAP-TH_L5.0-W2.5-P5.00-D1.0")
      (fields
        (field (name "Manufacturer Part") "CC1H104MC1FD3F6C10MF")
        (field (name "Manufacturer") "Dersonic(德尔创)")
      )
      (libsource (lib "easyedapro") (part "CC1H104MC1FD3F6C10MF"))
    )
    (comp (ref "C45")
      (value "1uF")
      (footprint "easyedapro:CAP-SMD_BD6.3-L6.6-W6.6-FD")
      (fields (field (name "Manufacturer Part") "189RV0019") (field (name "Manufacturer") "KNSCHA(科尼盛)"))
      (libsource (lib "easyedapro") (part "189RV0019"))
    )
    (comp (ref "C46")
      (value "1uF")
      (footprint "easyedapro:CAP-SMD_BD6.3-L6.6-W6.6-FD")
      (fields (field (name "Manufacturer Part") "189RV0019") (field (name "Manufacturer") "KNSCHA(科尼盛)"))
      (libsource (lib "easyedapro") (part "189RV0019"))
    )
    (comp (ref "C47")
      (value "100nF")
      (footprint "easyedapro:CAP-TH_L5.0-W2.5-P5.00-D1.0")
      (fields
        (field (name "Manufacturer Part") "CC1H104MC1FD3F6C10MF")
        (field (name "Manufacturer") "Dersonic(德尔创)")
      )
      (libsource (lib "easyedapro") (part "CC1H104MC1FD3F6C10MF"))
    )
    (comp (ref "C48")
      (value "1uF")
      (footprint "easyedapro:CAP-SMD_BD6.3-L6.6-W6.6-FD")
      (fields (field (name "Manufacturer Part") "189RV0019") (field (name "Manufacturer") "KNSCHA(科尼盛)"))
      (libsource (lib "easyedapro") (part "189RV0019"))
    )
    (comp (ref "C49")
      (value "1uF")
      (footprint "easyedapro:CAP-SMD_BD6.3-L6.6-W6.6-FD")
      (fields (field (name "Manufacturer Part") "189RV0019") (field (name "Manufacturer") "KNSCHA(科尼盛)"))
      (libsource (lib "easyedapro") (part "189RV0019"))
    )
    (comp (ref "C50")
      (value "100nF")
      (footprint "easyedapro:CAP-TH_L5.0-W2.5-P5.00-D1.0")
      (fields
        (field (name "Manufacturer Part") "CC1H104MC1FD3F6C10MF")
        (field (name "Manufacturer") "Dersonic(德尔创)")
      )
      (libsource (lib "easyedapro") (part "CC1H104MC1FD3F6C10MF"))
    )
    (comp (ref "C51")
      (value "1uF")
      (footprint "easyedapro:CAP-SMD_BD6.3-L6.6-W6.6-FD")
      (fields (field (name "Manufacturer Part") "189RV0019") (field (name "Manufacturer") "KNSCHA(科尼盛)"))
      (libsource (lib "easyedapro") (part "189RV0019"))
    )
    (comp (ref "C52")
      (value "1uF")
      (footprint "easyedapro:CAP-SMD_BD6.3-L6.6-W6.6-FD")
      (fields (field (name "Manufacturer Part") "189RV0019") (field (name "Manufacturer") "KNSCHA(科尼盛)"))
      (libsource (lib "easyedapro") (part "189RV0019"))
    )
    (comp (ref "C53")
      (value "100nF")
      (footprint "easyedapro:CAP-TH_L5.0-W2.5-P5.00-D1.0")
      (fields
        (field (name "Manufacturer Part") "CC1H104MC1FD3F6C10MF")
        (field (name "Manufacturer") "Dersonic(德尔创)")
      )
      (libsource (lib "easyedapro") (part "CC1H104MC1FD3F6C10MF"))
    )
    (comp (ref "D45")
      (value "1N4148PF")
      (footprint "easyedapro:Diode_THT:D_DO-35_SOD27_P7.62mm_Horizontal")
      (fields (field (name "Manufacturer") "ST(先科)"))
      (libsource (lib "easyedapro") (part "Diode_1N4148"))
    )
    (comp (ref "D46")
      (value "1N4148PF")
      (footprint "easyedapro:Diode_THT:D_DO-35_SOD27_P7.62mm_Horizontal")
      (fields (field (name "Manufacturer") "ST(先科)"))
      (libsource (lib "easyedapro") (part "Diode_1N4148"))
    )
    (comp (ref "D47")
      (value "1N4148PF")
      (footprint "easyedapro:Diode_THT:D_DO-35_SOD27_P7.62mm_Horizontal")
      (fields (field (name "Manufacturer") "ST(先科)"))
      (libsource (lib "easyedapro") (part "Diode_1N4148"))
    )
    (comp (ref "D48")
      (value "1N4148PF")
      (footprint "easyedapro:Diode_THT:D_DO-35_SOD27_P7.62mm_Horizontal")
      (fields (field (name "Manufacturer") "ST(先科)"))
      (libsource (lib "easyedapro") (part "Diode_1N4148"))
    )
    (comp (ref "D49")
      (value "1N4148PF")
      (footprint "easyedapro:Diode_THT:D_DO-35_SOD27_P7.62mm_Horizontal")
      (fields (field (name "Manufacturer") "ST(先科)"))
      (libsource (lib "easyedapro") (part "Diode_1N4148"))
    )
    (comp (ref "D50")
      (value "1N4148PF")
      (footprint "easyedapro:Diode_THT:D_DO-35_SOD27_P7.62mm_Horizontal")
      (fields (field (name "Manufacturer") "ST(先科)"))
      (libsource (lib "easyedapro") (part "Diode_1N4148"))
    )
    (comp (ref "J4")
      (value "HC-PJ-320A")
      (footprint "easyedapro:AUDIO-SMD_HC-PJ-320A")
      (fields (field (name "Manufacturer") "HC(虹成电子)"))
      (libsource (lib "easyedapro") (part "HC-PJ-320A"))
    )
    (comp (ref "J5")
      (value "HC-PJ-320A")
      (footprint "easyedapro:AUDIO-SMD_HC-PJ-320A")
      (fields (field (name "Manufacturer") "HC(虹成电子)"))
      (libsource (lib "easyedapro") (part "HC-PJ-320A"))
    )
    (comp (ref "J6")
      (value "HC-PJ-320A")
      (footprint "easyedapro:AUDIO-SMD_HC-PJ-320A")
      (fields (field (name "Manufacturer") "HC(虹成电子)"))
      (libsource (lib "easyedapro") (part "HC-PJ-320A"))
    )
    (comp (ref "J7")
      (value "HC-PJ-320A")
      (footprint "easyedapro:AUDIO-SMD_HC-PJ-320A")
      (fields (field (name "Manufacturer") "HC(虹成电子)"))
      (libsource (lib "easyedapro") (part "HC-PJ-320A"))
    )
    (comp (ref "J8")
      (value "HC-PJ-320A")
      (footprint "easyedapro:AUDIO-SMD_HC-PJ-320A")
      (fields (field (name "Manufacturer") "HC(虹成电子)"))
      (libsource (lib "easyedapro") (part "HC-PJ-320A"))
    )
    (comp (ref "J9")
      (value "HC-PJ-320A")
      (footprint "easyedapro:AUDIO-SMD_HC-PJ-320A")
      (fields (field (name "Manufacturer") "HC(虹成电子)"))
      (libsource (lib "easyedapro") (part "HC-PJ-320A"))
    )
    (comp (ref "R22")
      (value "100kΩ")
      (footprint "easyedapro:Resistor_THT:R_Axial_DIN0204_L3.6mm_D1.6mm_P2.54mm_Vertical")
      (fields
        (field (name "Manufacturer Part") "RN 1/8W 4K7 F T/B A1")
        (field (name "Manufacturer") "Tyohm(幸亚电阻)")
      )
      (libsource (lib "easyedapro") (part "Device_R"))
    )
    (comp (ref "R23")
      (value "10kΩ")
      (footprint "easyedapro:Resistor_THT:R_Axial_DIN0204_L3.6mm_D1.6mm_P2.54mm_Vertical")
      (fields
        (field (name "Manufacturer Part") "RN 1/8W 4K7 F T/B A1")
        (field (name "Manufacturer") "Tyohm(幸亚电阻)")
      )
      (libsource (lib "easyedapro") (part "Device_R"))
    )
    (comp (ref "R24")
      (value "20kΩ")
      (footprint "easyedapro:Resistor_THT:R_Axial_DIN0204_L3.6mm_D1.6mm_P2.54mm_Vertical")
      (fields
        (field (name "Manufacturer Part") "RN 1/8W 4K7 F T/B A1")
        (field (name "Manufacturer") "Tyohm(幸亚电阻)")
      )
      (libsource (lib "easyedapro") (part "Device_R"))
    )
    (comp (ref "R25")
      (value "4.7kΩ")
      (footprint "easyedapro:Resistor_THT:R_Axial_DIN0204_L3.6mm_D1.6mm_P2.54mm_Vertical")
      (fields
        (field (name "Manufacturer Part") "RN 1/8W 4K7 F T/B A1")
        (field (name "Manufacturer") "Tyohm(幸亚电阻)")
      )
      (libsource (lib "easyedapro") (part "Device_R"))
    )
    (comp (ref "R48")
      (value "100kΩ")
      (footprint "easyedapro:Resistor_THT:R_Axial_DIN0204_L3.6mm_D1.6mm_P2.54mm_Vertical")
      (fields
        (field (name "Manufacturer Part") "RN 1/8W 4K7 F T/B A1")
        (field (name "Manufacturer") "Tyohm(幸亚电阻)")
      )
      (libsource (lib "easyedapro") (part "Device_R"))
    )
    (comp (ref "R49")
      (value "10kΩ")
      (footprint "easyedapro:Resistor_THT:R_Axial_DIN0204_L3.6mm_D1.6mm_P2.54mm_Vertical")
      (fields
        (field (name "Manufacturer Part") "RN 1/8W 4K7 F T/B A1")
        (field (name "Manufacturer") "Tyohm(幸亚电阻)")
      )
      (libsource (lib "easyedapro") (part "Device_R"))
    )
    (comp (ref "R50")
      (value "20kΩ")
      (footprint "easyedapro:Resistor_THT:R_Axial_DIN0204_L3.6mm_D1.6mm_P2.54mm_Vertical")
      (fields
        (field (name "Manufacturer Part") "RN 1/8W 4K7 F T/B A1")
        (field (name "Manufacturer") "Tyohm(幸亚电阻)")
      )
      (libsource (lib "easyedapro") (part "Device_R"))
    )
    (comp (ref "R51")
      (value "4.7kΩ")
      (footprint "easyedapro:Resistor_THT:R_Axial_DIN0204_L3.6mm_D1.6mm_P2.54mm_Vertical")
      (fields
        (field (name "Manufacturer Part") "RN 1/8W 4K7 F T/B A1")
        (field (name "Manufacturer") "Tyohm(幸亚电阻)")
      )
      (libsource (lib "easyedapro") (part "Device_R"))
    )
    (comp (ref "R52")
      (value "100kΩ")
      (footprint "easyedapro:Resistor_THT:R_Axial_DIN0204_L3.6mm_D1.6mm_P2.54mm_Vertical")
      (fields
        (field (name "Manufacturer Part") "RN 1/8W 4K7 F T/B A1")
        (field (name "Manufacturer") "Tyohm(幸亚电阻)")
      )
      (libsource (lib "easyedapro") (part "Device_R"))
    )
    (comp (ref "R53")
      (value "10kΩ")
      (footprint "easyedapro:Resistor_THT:R_Axial_DIN0204_L3.6mm_D1.6mm_P2.54mm_Vertical")
      (fields
        (field (name "Manufacturer Part") "RN 1/8W 4K7 F T/B A1")
        (field (name "Manufacturer") "Tyohm(幸亚电阻)")
      )
      (libsource (lib "easyedapro") (part "Device_R"))
    )
    (comp (ref "R54")
      (value "20kΩ")
      (footprint "easyedapro:Resistor_THT:R_Axial_DIN0204_L3.6mm_D1.6mm_P2.54mm_Vertical")
      (fields
        (field (name "Manufacturer Part") "RN 1/8W 4K7 F T/B A1")
        (field (name "Manufacturer") "Tyohm(幸亚电阻)")
      )
      (libsource (lib "easyedapro") (part "Device_R"))
    )
    (comp (ref "R55")
      (value "4.7kΩ")
      (footprint "easyedapro:Resistor_THT:R_Axial_DIN0204_L3.6mm_D1.6mm_P2.54mm_Vertical")
      (fields
        (field (name "Manufacturer Part") "RN 1/8W 4K7 F T/B A1")
        (field (name "Manufacturer") "Tyohm(幸亚电阻)")
      )
      (libsource (lib "easyedapro") (part "Device_R"))
    )
    (comp (ref "R56")
      (value "100kΩ")
      (footprint "easyedapro:Resistor_THT:R_Axial_DIN0204_L3.6mm_D1.6mm_P2.54mm_Vertical")
      (fields
        (field (name "Manufacturer Part") "RN 1/8W 4K7 F T/B A1")
        (field (name "Manufacturer") "Tyohm(幸亚电阻)")
      )
      (libsource (lib "easyedapro") (part "Device_R"))
    )
    (comp (ref "R57")
      (value "10kΩ")
      (footprint "easyedapro:Resistor_THT:R_Axial_DIN0204_L3.6mm_D1.6mm_P2.54mm_Vertical")
      (fields
        (field (name "Manufacturer Part") "RN 1/8W 4K7 F T/B A1")
        (field (name "Manufacturer") "Tyohm(幸亚电阻)")
      )
      (libsource (lib "easyedapro") (part "Device_R"))
    )
    (comp (ref "R58")
      (value "20kΩ")
      (footprint "easyedapro:Resistor_THT:R_Axial_DIN0204_L3.6mm_D1.6mm_P2.54mm_Vertical")
      (fields
        (field (name "Manufacturer Part") "RN 1/8W 4K7 F T/B A1")
        (field (name "Manufacturer") "Tyohm(幸亚电阻)")
      )
      (libsource (lib "easyedapro") (part "Device_R"))
    )
    (comp (ref "R59")
      (value "4.7kΩ")
      (footprint "easyedapro:Resistor_THT:R_Axial_DIN0204_L3.6mm_D1.6mm_P2.54mm_Vertical")
      (fields
        (field (name "Manufacturer Part") "RN 1/8W 4K7 F T/B A1")
        (field (name "Manufacturer") "Tyohm(幸亚电阻)")
      )
      (libsource (lib "easyedapro") (part "Device_R"))
    )
    (comp (ref "R60")
      (value "100kΩ")
      (footprint "easyedapro:Resistor_THT:R_Axial_DIN0204_L3.6mm_D1.6mm_P2.54mm_Vertical")
      (fields
        (field (name "Manufacturer Part") "RN 1/8W 4K7 F T/B A1")
        (field (name "Manufacturer") "Tyohm(幸亚电阻)")
      )
      (libsource (lib "easyedapro") (part "Device_R"))
    )
    (comp (ref "R61")
      (value "10kΩ")
      (footprint "easyedapro:Resistor_THT:R_Axial_DIN0204_L3.6mm_D1.6mm_P2.54mm_Vertical")
      (fields
        (field (name "Manufacturer Part") "RN 1/8W 4K7 F T/B A1")
        (field (name "Manufacturer") "Tyohm(幸亚电阻)")
      )
      (libsource (lib "easyedapro") (part "Device_R"))
    )
    (comp (ref "R62")
      (value "20kΩ")
      (footprint "easyedapro:Resistor_THT:R_Axial_DIN0204_L3.6mm_D1.6mm_P2.54mm_Vertical")
      (fields
        (field (name "Manufacturer Part") "RN 1/8W 4K7 F T/B A1")
        (field (name "Manufacturer") "Tyohm(幸亚电阻)")
      )
      (libsource (lib "easyedapro") (part "Device_R"))
    )
    (comp (ref "R63")
      (value "4.7kΩ")
      (footprint "easyedapro:Resistor_THT:R_Axial_DIN0204_L3.6mm_D1.6mm_P2.54mm_Vertical")
      (fields
        (field (name "Manufacturer Part") "RN 1/8W 4K7 F T/B A1")
        (field (name "Manufacturer") "Tyohm(幸亚电阻)")
      )
      (libsource (lib "easyedapro") (part "Device_R"))
    )
    (comp (ref "R64")
      (value "100kΩ")
      (footprint "easyedapro:Resistor_THT:R_Axial_DIN0204_L3.6mm_D1.6mm_P2.54mm_Vertical")
      (fields
        (field (name "Manufacturer Part") "RN 1/8W 4K7 F T/B A1")
        (field (name "Manufacturer") "Tyohm(幸亚电阻)")
      )
      (libsource (lib "easyedapro") (part "Device_R"))
    )
    (comp (ref "R65")
      (value "10kΩ")
      (footprint "easyedapro:Resistor_THT:R_Axial_DIN0204_L3.6mm_D1.6mm_P2.54mm_Vertical")
      (fields
        (field (name "Manufacturer Part") "RN 1/8W 4K7 F T/B A1")
        (field (name "Manufacturer") "Tyohm(幸亚电阻)")
      )
      (libsource (lib "easyedapro") (part "Device_R"))
    )
    (comp (ref "R66")
      (value "20kΩ")
      (footprint "easyedapro:Resistor_THT:R_Axial_DIN0204_L3.6mm_D1.6mm_P2.54mm_Vertical")
      (fields
        (field (name "Manufacturer Part") "RN 1/8W 4K7 F T/B A1")
        (field (name "Manufacturer") "Tyohm(幸亚电阻)")
      )
      (libsource (lib "easyedapro") (part "Device_R"))
    )
    (comp (ref "R67")
      (value "4.7kΩ")
      (footprint "easyedapro:Resistor_THT:R_Axial_DIN0204_L3.6mm_D1.6mm_P2.54mm_Vertical")
      (fields
        (field (name "Manufacturer Part") "RN 1/8W 4K7 F T/B A1")
        (field (name "Manufacturer") "Tyohm(幸亚电阻)")
      )
      (libsource (lib "easyedapro") (part "Device_R"))
    )
    (comp (ref "U15")
      (value "MCP6002DRG")
      (footprint "easyedapro:SOP-8_L4.9-W3.9-P1.27-LS6.0-BL")
      (fields (field (name "Manufacturer") "HGC(深圳汉芯)"))
      (libsource (lib "easyedapro") (part "MCP6002DRG"))
    )
    (comp (ref "U16")
      (value "MCP6002DRG")
      (footprint "easyedapro:SOP-8_L4.9-W3.9-P1.27-LS6.0-BL")
      (fields (field (name "Manufacturer") "HGC(深圳汉芯)"))
      (libsource (lib "easyedapro") (part "MCP6002DRG"))
    )
    (comp (ref "U17")
      (value "MCP6002DRG")
      (footprint "easyedapro:SOP-8_L4.9-W3.9-P1.27-LS6.0-BL")
      (fields (field (name "Manufacturer") "HGC(深圳汉芯)"))
      (libsource (lib "easyedapro") (part "MCP6002DRG"))
    )
    (comp (ref "U18")
      (value "MCP6002DRG")
      (footprint "easyedapro:SOP-8_L4.9-W3.9-P1.27-LS6.0-BL")
      (fields (field (name "Manufacturer") "HGC(深圳汉芯)"))
      (libsource (lib "easyedapro") (part "MCP6002DRG"))
    )
    (comp (ref "U19")
      (value "MCP6002DRG")
      (footprint "easyedapro:SOP-8_L4.9-W3.9-P1.27-LS6.0-BL")
      (fields (field (name "Manufacturer") "HGC(深圳汉芯)"))
      (libsource (lib "easyedapro") (part "MCP6002DRG"))
    )
    (comp (ref "U20")
      (value "MCP6002DRG")
      (footprint "easyedapro:SOP-8_L4.9-W3.9-P1.27-LS6.0-BL")
      (fields (field (name "Manufacturer") "HGC(深圳汉芯)"))
      (libsource (lib "easyedapro") (part "MCP6002DRG"))
    )
    (comp (ref "C5")
      (value "220uF")
      (footprint "easyedapro:CAP-SMD_BD6.3-L6.6-W6.6-FD")
      (fields (field (name "Manufacturer Part") "189RV0019") (field (name "Manufacturer") "KNSCHA(科尼盛)"))
      (libsource (lib "easyedapro") (part "189RV0019"))
    )
    (comp (ref "C6")
      (value "100nF")
      (footprint "easyedapro:CAP-TH_L5.0-W2.5-P5.00-D1.0")
      (fields
        (field (name "Manufacturer Part") "CC1H104MC1FD3F6C10MF")
        (field (name "Manufacturer") "Dersonic(德尔创)")
      )
      (libsource (lib "easyedapro") (part "CC1H104MC1FD3F6C10MF"))
    )
    (comp (ref "C7")
      (value "100uF")
      (footprint "easyedapro:C1206")
      (description "Capacitance:100uF Tolerance:±20% Tolerance:±20% Voltage Rating:10V Temperature Coefficient:X5R")
      (fields
        (field (name "Manufacturer Part") "HGC1206R5107M100NSPJ")
        (field (name "Manufacturer") "Chinocera(华瓷)")
      )
      (libsource (lib "easyedapro") (part "HGC1206R5107M100NSPJ"))
    )
    (comp (ref "C8")
      (value "1uF")
      (footprint "easyedapro:Capacitor_THT:C_Disc_D3.4mm_W2.1mm_P2.50mm")
      (description "Capacitance:100nF Tolerance:±10% Tolerance:±10% Voltage Rating:63V Temperature Coefficient:-")
      (fields
        (field (name "Manufacturer Part") "CT4G-0805-2X1-63V-0.1μF-K")
        (field (name "Manufacturer") "TORCH(火炬)")
      )
      (libsource (lib "easyedapro") (part "Device_C"))
    )
    (comp (ref "C9")
      (value "100nF")
      (footprint "easyedapro:Capacitor_THT:C_Disc_D3.4mm_W2.1mm_P2.50mm")
      (description "Capacitance:100nF Tolerance:±10% Tolerance:±10% Voltage Rating:63V Temperature Coefficient:-")
      (fields
        (field (name "Manufacturer Part") "CT4G-0805-2X1-63V-0.1μF-K")
        (field (name "Manufacturer") "TORCH(火炬)")
      )
      (libsource (lib "easyedapro") (part "Device_C"))
    )
    (comp (ref "D44")
      (value "SA6.0A")
      (footprint "easyedapro:DO-15_BD3.1-L6.7-P10.70-D0.8-RD")
      (fields (field (name "Manufacturer") "Littelfuse(美国力特)"))
      (libsource (lib "easyedapro") (part "SA6.0A_C1973281"))
    )
    (comp (ref "F1")
      (value "nSMD050-33V")
      (footprint "easyedapro:F1206")
      (description "Voltage - Max:33V Current - Max:100A Hold Current:500mA Trip Current:1A")
      (fields (field (name "Manufacturer") "台湾陆海"))
      (libsource (lib "easyedapro") (part "nSMD050-33V"))
    )
    (comp (ref "J1")
      (value "DC005")
      (footprint "easyedapro:DC-IN-TH_DC005")
      (fields (field (name "Manufacturer") "SHOU HAN(首韩)"))
      (libsource (lib "easyedapro") (part "DC005_C431533"))
    )
    (comp (ref "R20")
      (value "33Ω")
      (footprint "easyedapro:Resistor_THT:R_Axial_DIN0204_L3.6mm_D1.6mm_P2.54mm_Vertical")
      (fields
        (field (name "Manufacturer Part") "RN1/8W10KFT/BA1")
        (field (name "Manufacturer") "Tyohm(幸亚电阻)")
      )
      (libsource (lib "easyedapro") (part "Device_R"))
    )
    (comp (ref "SW1")
      (value "HX B3F-4055-Y")
      (footprint "easyedapro:Button_Switch_SMD:SW_SPST_PTS645")
      (fields (field (name "Manufacturer") "hanxia(韩下)"))
      (libsource (lib "easyedapro") (part "Switch_SW_Push"))
    )
    (comp (ref "SW2")
      (value "HX B3F-4055-Y")
      (footprint "easyedapro:Button_Switch_SMD:SW_SPST_PTS645")
      (fields (field (name "Manufacturer") "hanxia(韩下)"))
      (libsource (lib "easyedapro") (part "Switch_SW_Push"))
    )
    (comp (ref "SW3")
      (value "HX B3F-4055-Y")
      (footprint "easyedapro:Button_Switch_SMD:SW_SPST_PTS645")
      (fields (field (name "Manufacturer") "hanxia(韩下)"))
      (libsource (lib "easyedapro") (part "Switch_SW_Push"))
    )
    (comp (ref "SW4")
      (value "HX B3F-4055-Y")
      (footprint "easyedapro:Button_Switch_SMD:SW_SPST_PTS645")
      (fields (field (name "Manufacturer") "hanxia(韩下)"))
      (libsource (lib "easyedapro") (part "Switch_SW_Push"))
    )
    (comp (ref "SW5")
      (value "HX B3F-4055-Y")
      (footprint "easyedapro:Button_Switch_SMD:SW_SPST_PTS645")
      (fields (field (name "Manufacturer") "hanxia(韩下)"))
      (libsource (lib "easyedapro") (part "Switch_SW_Push"))
    )
    (comp (ref "SW6")
      (value "HX B3F-4055-Y")
      (footprint "easyedapro:Button_Switch_SMD:SW_SPST_PTS645")
      (fields (field (name "Manufacturer") "hanxia(韩下)"))
      (libsource (lib "easyedapro") (part "Switch_SW_Push"))
    )
    (comp (ref "SW7")
      (value "HX B3F-4055-Y")
      (footprint "easyedapro:Button_Switch_SMD:SW_SPST_PTS645")
      (fields (field (name "Manufacturer") "hanxia(韩下)"))
      (libsource (lib "easyedapro") (part "Switch_SW_Push"))
    )
    (comp (ref "SW8")
      (value "HX B3F-4055-Y")
      (footprint "easyedapro:Button_Switch_SMD:SW_SPST_PTS645")
      (fields (field (name "Manufacturer") "hanxia(韩下)"))
      (libsource (lib "easyedapro") (part "Switch_SW_Push"))
    )
    (comp (ref "SW9")
      (value "HX B3F-4055-Y")
      (footprint "easyedapro:Button_Switch_SMD:SW_SPST_PTS645")
      (fields (field (name "Manufacturer") "hanxia(韩下)"))
      (libsource (lib "easyedapro") (part "Switch_SW_Push"))
    )
    (comp (ref "SW10")
      (value "HX B3F-4055-Y")
      (footprint "easyedapro:Button_Switch_SMD:SW_SPST_PTS645")
      (fields (field (name "Manufacturer") "hanxia(韩下)"))
      (libsource (lib "easyedapro") (part "Switch_SW_Push"))
    )
    (comp (ref "SW11")
      (value "HX B3F-4055-Y")
      (footprint "easyedapro:Button_Switch_SMD:SW_SPST_PTS645")
      (fields (field (name "Manufacturer") "hanxia(韩下)"))
      (libsource (lib "easyedapro") (part "Switch_SW_Push"))
    )
    (comp (ref "SW12")
      (value "HX B3F-4055-Y")
      (footprint "easyedapro:Button_Switch_SMD:SW_SPST_PTS645")
      (fields (field (name "Manufacturer") "hanxia(韩下)"))
      (libsource (lib "easyedapro") (part "Switch_SW_Push"))
    )
    (comp (ref "SW13")
      (value "HX B3F-4055-Y")
      (footprint "easyedapro:Button_Switch_SMD:SW_SPST_PTS645")
      (fields (field (name "Manufacturer") "hanxia(韩下)"))
      (libsource (lib "easyedapro") (part "Switch_SW_Push"))
    )
    (comp (ref "SW14")
      (value "HX B3F-4055-Y")
      (footprint "easyedapro:Button_Switch_SMD:SW_SPST_PTS645")
      (fields (field (name "Manufacturer") "hanxia(韩下)"))
      (libsource (lib "easyedapro") (part "Switch_SW_Push"))
    )
    (comp (ref "SW15")
      (value "HX B3F-4055-Y")
      (footprint "easyedapro:Button_Switch_SMD:SW_SPST_PTS645")
      (fields (field (name "Manufacturer") "hanxia(韩下)"))
      (libsource (lib "easyedapro") (part "Switch_SW_Push"))
    )
    (comp (ref "SW16")
      (value "HX B3F-4055-Y")
      (footprint "easyedapro:Button_Switch_SMD:SW_SPST_PTS645")
      (fields (field (name "Manufacturer") "hanxia(韩下)"))
      (libsource (lib "easyedapro") (part "Switch_SW_Push"))
    )
    (comp (ref "SW17")
      (value "HX B3F-4055-Y")
      (footprint "easyedapro:Button_Switch_SMD:SW_SPST_PTS645")
      (fields (field (name "Manufacturer") "hanxia(韩下)"))
      (libsource (lib "easyedapro") (part "Switch_SW_Push"))
    )
    (comp (ref "SW18")
      (value "HX B3F-4055-Y")
      (footprint "easyedapro:Button_Switch_SMD:SW_SPST_PTS645")
      (fields (field (name "Manufacturer") "hanxia(韩下)"))
      (libsource (lib "easyedapro") (part "Switch_SW_Push"))
    )
    (comp (ref "SW19")
      (value "HX B3F-4055-Y")
      (footprint "easyedapro:Button_Switch_SMD:SW_SPST_PTS645")
      (fields (field (name "Manufacturer") "hanxia(韩下)"))
      (libsource (lib "easyedapro") (part "Switch_SW_Push"))
    )
    (comp (ref "SW20")
      (value "HX B3F-4055-Y")
      (footprint "easyedapro:Button_Switch_SMD:SW_SPST_PTS645")
      (fields (field (name "Manufacturer") "hanxia(韩下)"))
      (libsource (lib "easyedapro") (part "Switch_SW_Push"))
    )
    (comp (ref "SW21")
      (value "HX B3F-4055-Y")
      (footprint "easyedapro:Button_Switch_SMD:SW_SPST_PTS645")
      (fields (field (name "Manufacturer") "hanxia(韩下)"))
      (libsource (lib "easyedapro") (part "Switch_SW_Push"))
    )
    (comp (ref "SW22")
      (value "HX B3F-4055-Y")
      (footprint "easyedapro:Button_Switch_SMD:SW_SPST_PTS645")
      (fields (field (name "Manufacturer") "hanxia(韩下)"))
      (libsource (lib "easyedapro") (part "Switch_SW_Push"))
    )
    (comp (ref "SW23")
      (value "HX B3F-4055-Y")
      (footprint "easyedapro:Button_Switch_SMD:SW_SPST_PTS645")
      (fields (field (name "Manufacturer") "hanxia(韩下)"))
      (libsource (lib "easyedapro") (part "Switch_SW_Push"))
    )
    (comp (ref "SW24")
      (value "HX B3F-4055-Y")
      (footprint "easyedapro:Button_Switch_SMD:SW_SPST_PTS645")
      (fields (field (name "Manufacturer") "hanxia(韩下)"))
      (libsource (lib "easyedapro") (part "Switch_SW_Push"))
    )
    (comp (ref "SW25")
      (value "HX B3F-4055-Y")
      (footprint "easyedapro:Button_Switch_SMD:SW_SPST_PTS645")
      (fields (field (name "Manufacturer") "hanxia(韩下)"))
      (libsource (lib "easyedapro") (part "Switch_SW_Push"))
    )
    (comp (ref "SW26")
      (value "HX B3F-4055-Y")
      (footprint "easyedapro:Button_Switch_SMD:SW_SPST_PTS645")
      (fields (field (name "Manufacturer") "hanxia(韩下)"))
      (libsource (lib "easyedapro") (part "Switch_SW_Push"))
    )
    (comp (ref "SW27")
      (value "HX B3F-4055-Y")
      (footprint "easyedapro:Button_Switch_SMD:SW_SPST_PTS645")
      (fields (field (name "Manufacturer") "hanxia(韩下)"))
      (libsource (lib "easyedapro") (part "Switch_SW_Push"))
    )
    (comp (ref "SW28")
      (value "HX B3F-4055-Y")
      (footprint "easyedapro:Button_Switch_SMD:SW_SPST_PTS645")
      (fields (field (name "Manufacturer") "hanxia(韩下)"))
      (libsource (lib "easyedapro") (part "Switch_SW_Push"))
    )
    (comp (ref "SW29")
      (value "HX B3F-4055-Y")
      (footprint "easyedapro:Button_Switch_SMD:SW_SPST_PTS645")
      (fields (field (name "Manufacturer") "hanxia(韩下)"))
      (libsource (lib "easyedapro") (part "Switch_SW_Push"))
    )
    (comp (ref "SW30")
      (value "HX B3F-4055-Y")
      (footprint "easyedapro:Button_Switch_SMD:SW_SPST_PTS645")
      (fields (field (name "Manufacturer") "hanxia(韩下)"))
      (libsource (lib "easyedapro") (part "Switch_SW_Push"))
    )
    (comp (ref "SW31")
      (value "HX B3F-4055-Y")
      (footprint "easyedapro:Button_Switch_SMD:SW_SPST_PTS645")
      (fields (field (name "Manufacturer") "hanxia(韩下)"))
      (libsource (lib "easyedapro") (part "Switch_SW_Push"))
    )
    (comp (ref "SW32")
      (value "HX B3F-4055-Y")
      (footprint "easyedapro:Button_Switch_SMD:SW_SPST_PTS645")
      (fields (field (name "Manufacturer") "hanxia(韩下)"))
      (libsource (lib "easyedapro") (part "Switch_SW_Push"))
    )
    (comp (ref "SW33")
      (value "HX B3F-4055-Y")
      (footprint "easyedapro:Button_Switch_SMD:SW_SPST_PTS645")
      (fields (field (name "Manufacturer") "hanxia(韩下)"))
      (libsource (lib "easyedapro") (part "Switch_SW_Push"))
    )
    (comp (ref "SW34")
      (value "HX B3F-4055-Y")
      (footprint "easyedapro:Button_Switch_SMD:SW_SPST_PTS645")
      (fields (field (name "Manufacturer") "hanxia(韩下)"))
      (libsource (lib "easyedapro") (part "Switch_SW_Push"))
    )
    (comp (ref "SW35")
      (value "HX B3F-4055-Y")
      (footprint "easyedapro:Button_Switch_SMD:SW_SPST_PTS645")
      (fields (field (name "Manufacturer") "hanxia(韩下)"))
      (libsource (lib "easyedapro") (part "Switch_SW_Push"))
    )
    (comp (ref "SW36")
      (value "HX B3F-4055-Y")
      (footprint "easyedapro:Button_Switch_SMD:SW_SPST_PTS645")
      (fields (field (name "Manufacturer") "hanxia(韩下)"))
      (libsource (lib "easyedapro") (part "Switch_SW_Push"))
    )
    (comp (ref "SW37")
      (value "HX B3F-4055-Y")
      (footprint "easyedapro:Button_Switch_SMD:SW_SPST_PTS645")
      (fields (field (name "Manufacturer") "hanxia(韩下)"))
      (libsource (lib "easyedapro") (part "Switch_SW_Push"))
    )
    (comp (ref "SW38")
      (value "HX B3F-4055-Y")
      (footprint "easyedapro:Button_Switch_SMD:SW_SPST_PTS645")
      (fields (field (name "Manufacturer") "hanxia(韩下)"))
      (libsource (lib "easyedapro") (part "Switch_SW_Push"))
    )
    (comp (ref "SW39")
      (value "HX B3F-4055-Y")
      (footprint "easyedapro:Button_Switch_SMD:SW_SPST_PTS645")
      (fields (field (name "Manufacturer") "hanxia(韩下)"))
      (libsource (lib "easyedapro") (part "Switch_SW_Push"))
    )
    (comp (ref "SW40")
      (value "HX B3F-4055-Y")
      (footprint "easyedapro:Button_Switch_SMD:SW_SPST_PTS645")
      (fields (field (name "Manufacturer") "hanxia(韩下)"))
      (libsource (lib "easyedapro") (part "Switch_SW_Push"))
    )
    (comp (ref "SW41")
      (value "HX B3F-4055-Y")
      (footprint "easyedapro:Button_Switch_SMD:SW_SPST_PTS645")
      (fields (field (name "Manufacturer") "hanxia(韩下)"))
      (libsource (lib "easyedapro") (part "Switch_SW_Push"))
    )
    (comp (ref "SW42")
      (value "HX B3F-4055-Y")
      (footprint "easyedapro:Button_Switch_SMD:SW_SPST_PTS645")
      (fields (field (name "Manufacturer") "hanxia(韩下)"))
      (libsource (lib "easyedapro") (part "Switch_SW_Push"))
    )
    (comp (ref "SW49")
      (value "TK-6580A-1")
      (footprint "easyedapro:SW-TH_TK-6580A-1")
      (fields (field (name "Manufacturer") "Yuandi(元迪)"))
      (libsource (lib "easyedapro") (part "TK-6580A-1"))
    )
    (comp (ref "U6")
      (value "1812L200/33GR")
      (footprint "easyedapro:F1812")
      (fields (field (name "Manufacturer") "LUTE(陆特)"))
      (libsource (lib "easyedapro") (part "1812L200/33GR"))
    )
    (comp (ref "U8")
      (value "SN74AHCT125N")
      (footprint "easyedapro:PDIP-14_L19.3-W6.4-P2.54-LS7.6-BL")
      (fields (field (name "Manufacturer") "TI(德州仪器)"))
      (libsource (lib "easyedapro") (part "SN74AHCT125N"))
    )
  )
  (nets
    (net (code "1") (name "3VDC") (class "Default")
      (node (ref "C25") (pin "2") (pinfunction "2_2") (pintype "unspecified"))
      (node (ref "C3") (pin "2") (pinfunction "~_2") (pintype "unspecified"))
      (node (ref "C4") (pin "2") (pinfunction "~_2") (pintype "unspecified"))
      (node (ref "C54") (pin "1") (pinfunction "~_1") (pintype "unspecified"))
      (node (ref "C56") (pin "1") (pinfunction "1_1") (pintype "input"))
      (node (ref "COL_MUX") (pin "24") (pinfunction "VCC_24") (pintype "unspecified"))
      (node (ref "R2") (pin "1") (pinfunction "~_1") (pintype "unspecified"))
      (node (ref "R69") (pin "1") (pinfunction "~_1") (pintype "unspecified"))
      (node (ref "ROW_MUX") (pin "24") (pinfunction "VCC_24") (pintype "unspecified"))
      (node (ref "RV1") (pin "1") (pinfunction "1_1") (pintype "unspecified"))
      (node (ref "RV2") (pin "1") (pinfunction "1_1") (pintype "unspecified"))
      (node (ref "RV3") (pin "1") (pinfunction "1_1") (pintype "unspecified"))
      (node (ref "SW43") (pin "2") (pinfunction "2_2") (pintype "unspecified"))
      (node (ref "SW44") (pin "2") (pinfunction "2_2") (pintype "unspecified"))
      (node (ref "SW45") (pin "2") (pinfunction "2_2") (pintype "unspecified"))
      (node (ref "SW46") (pin "2") (pinfunction "2_2") (pintype "unspecified"))
      (node (ref "SW47") (pin "2") (pinfunction "2_2") (pintype "unspecified"))
      (node (ref "SW48") (pin "2") (pinfunction "2_2") (pintype "unspecified"))
      (node (ref "Screen") (pin "2") (pinfunction "Pin_2_2") (pintype "unspecified"))
      (node (ref "U1") (pin "3.3V_2") (pinfunction "3.3V_2_3.3V_2") (pintype "unspecified"))
      (node (ref "U15") (pin "8") (pinfunction "VDD_8") (pintype "unspecified"))
    )
    (net (code "2") (name "5VDC") (class "Default")
      (node (ref "C10") (pin "2") (pinfunction "~_2") (pintype "unspecified"))
      (node (ref "C8") (pin "1") (pinfunction "~_1") (pintype "unspecified"))
      (node (ref "C9") (pin "1") (pinfunction "~_1") (pintype "unspecified"))
      (node (ref "R4") (pin "2") (pinfunction "~_2") (pintype "unspecified"))
      (node (ref "SW49") (pin "5") (pinfunction "5_5") (pintype "unspecified"))
      (node (ref "U5") (pin "7") (pinfunction "VO1_7") (pintype "unspecified"))
      (node (ref "U8") (pin "14") (pinfunction "VCC_14") (pintype "unspecified"))
    )
    (net (code "3") (name "COL1") (class "Default")
      (node (ref "COL_MUX") (pin "9") (pinfunction "I0_9") (pintype "unspecified"))
      (node (ref "SW1") (pin "2") (pinfunction "2_2") (pintype "unspecified"))
      (node (ref "SW2") (pin "2") (pinfunction "2_2") (pintype "unspecified"))
      (node (ref "SW3") (pin "2") (pinfunction "2_2") (pintype "unspecified"))
      (node (ref "SW4") (pin "2") (pinfunction "2_2") (pintype "unspecified"))
      (node (ref "SW5") (pin "2") (pinfunction "2_2") (pintype "unspecified"))
      (node (ref "SW6") (pin "2") (pinfunction "2_2") (pintype "unspecified"))
      (node (ref "SW7") (pin "2") (pinfunction "2_2") (pintype "unspecified"))
    )
    (net (code "4") (name "COL2") (class "Default")
      (node (ref "COL_MUX") (pin "8") (pinfunction "I1_8") (pintype "unspecified"))
      (node (ref "SW10") (pin "2") (pinfunction "2_2") (pintype "unspecified"))
      (node (ref "SW11") (pin "2") (pinfunction "2_2") (pintype "unspecified"))
      (node (ref "SW12") (pin "2") (pinfunction "2_2") (pintype "unspecified"))
      (node (ref "SW13") (pin "2") (pinfunction "2_2") (pintype "unspecified"))
      (node (ref "SW14") (pin "2") (pinfunction "2_2") (pintype "unspecified"))
      (node (ref "SW8") (pin "2") (pinfunction "2_2") (pintype "unspecified"))
      (node (ref "SW9") (pin "2") (pinfunction "2_2") (pintype "unspecified"))
    )
    (net (code "5") (name "COL3") (class "Default")
      (node (ref "COL_MUX") (pin "7") (pinfunction "I2_7") (pintype "unspecified"))
      (node (ref "SW15") (pin "2") (pinfunction "2_2") (pintype "unspecified"))
      (node (ref "SW16") (pin "2") (pinfunction "2_2") (pintype "unspecified"))
      (node (ref "SW17") (pin "2") (pinfunction "2_2") (pintype "unspecified"))
      (node (ref "SW18") (pin "2") (pinfunction "2_2") (pintype "unspecified"))
      (node (ref "SW19") (pin "2") (pinfunction "2_2") (pintype "unspecified"))
      (node (ref "SW20") (pin "2") (pinfunction "2_2") (pintype "unspecified"))
      (node (ref "SW21") (pin "2") (pinfunction "2_2") (pintype "unspecified"))
    )
    (net (code "6") (name "COL4") (class "Default")
      (node (ref "COL_MUX") (pin "6") (pinfunction "I3_6") (pintype "unspecified"))
      (node (ref "SW22") (pin "2") (pinfunction "2_2") (pintype "unspecified"))
      (node (ref "SW23") (pin "2") (pinfunction "2_2") (pintype "unspecified"))
      (node (ref "SW24") (pin "2") (pinfunction "2_2") (pintype "unspecified"))
      (node (ref "SW25") (pin "2") (pinfunction "2_2") (pintype "unspecified"))
      (node (ref "SW26") (pin "2") (pinfunction "2_2") (pintype "unspecified"))
      (node (ref "SW27") (pin "2") (pinfunction "2_2") (pintype "unspecified"))
      (node (ref "SW28") (pin "2") (pinfunction "2_2") (pintype "unspecified"))
    )
    (net (code "7") (name "COL5") (class "Default")
      (node (ref "COL_MUX") (pin "5") (pinfunction "I4_5") (pintype "unspecified"))
      (node (ref "SW29") (pin "2") (pinfunction "2_2") (pintype "unspecified"))
      (node (ref "SW30") (pin "2") (pinfunction "2_2") (pintype "unspecified"))
      (node (ref "SW31") (pin "2") (pinfunction "2_2") (pintype "unspecified"))
      (node (ref "SW32") (pin "2") (pinfunction "2_2") (pintype "unspecified"))
      (node (ref "SW33") (pin "2") (pinfunction "2_2") (pintype "unspecified"))
      (node (ref "SW34") (pin "2") (pinfunction "2_2") (pintype "unspecified"))
      (node (ref "SW35") (pin "2") (pinfunction "2_2") (pintype "unspecified"))
    )
    (net (code "8") (name "COL6") (class "Default")
      (node (ref "COL_MUX") (pin "4") (pinfunction "I5_4") (pintype "unspecified"))
      (node (ref "SW36") (pin "2") (pinfunction "2_2") (pintype "unspecified"))
      (node (ref "SW37") (pin "2") (pinfunction "2_2") (pintype "unspecified"))
      (node (ref "SW38") (pin "2") (pinfunction "2_2") (pintype "unspecified"))
      (node (ref "SW39") (pin "2") (pinfunction "2_2") (pintype "unspecified"))
      (node (ref "SW40") (pin "2") (pinfunction "2_2") (pintype "unspecified"))
      (node (ref "SW41") (pin "2") (pinfunction "2_2") (pintype "unspecified"))
      (node (ref "SW42") (pin "2") (pinfunction "2_2") (pintype "unspecified"))
    )
    (net (code "9") (name "CTRL1") (class "Default")
      (node (ref "COL_MUX") (pin "2") (pinfunction "I7_2") (pintype "unspecified"))
      (node (ref "SW43") (pin "1") (pinfunction "1_1") (pintype "unspecified"))
    )
    (net (code "10") (name "CTRL2") (class "Default")
      (node (ref "COL_MUX") (pin "23") (pinfunction "I8_23") (pintype "unspecified"))
      (node (ref "SW44") (pin "1") (pinfunction "1_1") (pintype "unspecified"))
    )
    (net (code "11") (name "CTRL3") (class "Default")
      (node (ref "COL_MUX") (pin "22") (pinfunction "I9_22") (pintype "unspecified"))
      (node (ref "SW45") (pin "1") (pinfunction "1_1") (pintype "unspecified"))
    )
    (net (code "12") (name "CTRL4") (class "Default")
      (node (ref "COL_MUX") (pin "21") (pinfunction "I10_21") (pintype "unspecified"))
      (node (ref "SW46") (pin "1") (pinfunction "1_1") (pintype "unspecified"))
    )
    (net (code "13") (name "CTRL5") (class "Default")
      (node (ref "COL_MUX") (pin "20") (pinfunction "I11_20") (pintype "unspecified"))
      (node (ref "SW47") (pin "1") (pinfunction "1_1") (pintype "unspecified"))
    )
    (net (code "14") (name "CTRL6") (class "Default")
      (node (ref "COL_MUX") (pin "19") (pinfunction "I12_19") (pintype "unspecified"))
      (node (ref "SW48") (pin "1") (pinfunction "1_1") (pintype "unspecified"))
    )
    (net (code "15") (name "E1") (class "Default")
      (node (ref "C12") (pin "1") (pinfunction "1_1") (pintype "input"))
      (node (ref "R25") (pin "2") (pinfunction "~_2") (pintype "unspecified"))
      (node (ref "U1") (pin "14") (pinfunction "14_14") (pintype "bidirectional"))
    )
    (net (code "16") (name "E2") (class "Default")
      (node (ref "C43") (pin "1") (pinfunction "1_1") (pintype "input"))
      (node (ref "R55") (pin "2") (pinfunction "~_2") (pintype "unspecified"))
      (node (ref "U1") (pin "15") (pinfunction "15_15") (pintype "bidirectional"))
    )
    (net (code "17") (name "E3") (class "Default")
      (node (ref "C46") (pin "1") (pinfunction "1_1") (pintype "input"))
      (node (ref "R59") (pin "2") (pinfunction "~_2") (pintype "unspecified"))
      (node (ref "U1") (pin "16") (pinfunction "16_16") (pintype "bidirectional"))
    )
    (net (code "18") (name "E4") (class "Default")
      (node (ref "C40") (pin "1") (pinfunction "1_1") (pintype "input"))
      (node (ref "R51") (pin "2") (pinfunction "~_2") (pintype "unspecified"))
      (node (ref "U1") (pin "17") (pinfunction "17_17") (pintype "bidirectional"))
    )
    (net (code "19") (name "E5") (class "Default")
      (node (ref "C49") (pin "1") (pinfunction "1_1") (pintype "input"))
      (node (ref "R63") (pin "2") (pinfunction "~_2") (pintype "unspecified"))
      (node (ref "U1") (pin "20") (pinfunction "20_20") (pintype "bidirectional"))
    )
    (net (code "20") (name "E6") (class "Default")
      (node (ref "C52") (pin "1") (pinfunction "1_1") (pintype "input"))
      (node (ref "R67") (pin "2") (pinfunction "~_2") (pintype "unspecified"))
      (node (ref "U1") (pin "21") (pinfunction "21_21") (pintype "bidirectional"))
    )
    (net (code "21") (name "FP1") (class "Default")
      (node (ref "COL_MUX") (pin "17") (pinfunction "I14_17") (pintype "unspecified"))
      (node (ref "RV1") (pin "2") (pinfunction "2_2") (pintype "unspecified"))
    )
    (net (code "22") (name "FP2") (class "Default")
      (node (ref "COL_MUX") (pin "16") (pinfunction "I15_16") (pintype "unspecified"))
      (node (ref "RV2") (pin "2") (pinfunction "2_2") (pintype "unspecified"))
    )
    (net (code "23") (name "GND") (class "Default")
      (node (ref "C10") (pin "1") (pinfunction "~_1") (pintype "unspecified"))
      (node (ref "C12") (pin "2") (pinfunction "2_2") (pintype "input"))
      (node (ref "C2") (pin "2") (pinfunction "~_2") (pintype "unspecified"))
      (node (ref "C3") (pin "1") (pinfunction "~_1") (pintype "unspecified"))
      (node (ref "C31") (pin "2") (pinfunction "~_2") (pintype "unspecified"))
      (node (ref "C32") (pin "2") (pinfunction "~_2") (pintype "unspecified"))
      (node (ref "C33") (pin "2") (pinfunction "~_2") (pintype "unspecified"))
      (node (ref "C34") (pin "2") (pinfunction "~_2") (pintype "unspecified"))
      (node (ref "C35") (pin "2") (pinfunction "~_2") (pintype "unspecified"))
      (node (ref "C36") (pin "2") (pinfunction "~_2") (pintype "unspecified"))
      (node (ref "C4") (pin "1") (pinfunction "~_1") (pintype "unspecified"))
      (node (ref "C40") (pin "2") (pinfunction "2_2") (pintype "input"))
      (node (ref "C43") (pin "2") (pinfunction "2_2") (pintype "input"))
      (node (ref "C46") (pin "2") (pinfunction "2_2") (pintype "input"))
      (node (ref "C49") (pin "2") (pinfunction "2_2") (pintype "input"))
      (node (ref "C5") (pin "1") (pinfunction "1_1") (pintype "input"))
      (node (ref "C52") (pin "2") (pinfunction "2_2") (pintype "input"))
      (node (ref "C54") (pin "2") (pinfunction "~_2") (pintype "unspecified"))
      (node (ref "C56") (pin "2") (pinfunction "2_2") (pintype "input"))
      (node (ref "C6") (pin "1") (pinfunction "1_1") (pintype "unspecified"))
      (node (ref "C7") (pin "1") (pinfunction "1_1") (pintype "unspecified"))
      (node (ref "C8") (pin "2") (pinfunction "~_2") (pintype "unspecified"))
      (node (ref "C9") (pin "2") (pinfunction "~_2") (pintype "unspecified"))
      (node (ref "COL_MUX") (pin "12") (pinfunction "GND_12") (pintype "unspecified"))
      (node (ref "COL_MUX") (pin "15") (pinfunction "~{E}_15") (pintype "input"))
      (node (ref "COL_MUX") (pin "3") (pinfunction "I6_3") (pintype "unspecified"))
      (node (ref "D42") (pin "3") (pinfunction "VSS_3") (pintype "unspecified"))
      (node (ref "D44") (pin "2") (pinfunction "A_2") (pintype "input"))
      (node (ref "J1") (pin "2") (pinfunction "2_2") (pintype "unspecified"))
      (node (ref "J1") (pin "3") (pinfunction "3_3") (pintype "unspecified"))
      (node (ref "J2") (pin "2") (pinfunction "2_2") (pintype "unspecified"))
      (node (ref "J3") (pin "2") (pinfunction "2_2") (pintype "unspecified"))
      (node (ref "J4") (pin "2") (pinfunction "2_2") (pintype "unspecified"))
      (node (ref "J4") (pin "3") (pinfunction "3_3") (pintype "unspecified"))
      (node (ref "J4") (pin "4") (pinfunction "4_4") (pintype "unspecified"))
      (node (ref "J5") (pin "2") (pinfunction "2_2") (pintype "unspecified"))
      (node (ref "J5") (pin "3") (pinfunction "3_3") (pintype "unspecified"))
      (node (ref "J5") (pin "4") (pinfunction "4_4") (pintype "unspecified"))
      (node (ref "J6") (pin "2") (pinfunction "2_2") (pintype "unspecified"))
      (node (ref "J6") (pin "3") (pinfunction "3_3") (pintype "unspecified"))
      (node (ref "J6") (pin "4") (pinfunction "4_4") (pintype "unspecified"))
      (node (ref "J7") (pin "2") (pinfunction "2_2") (pintype "unspecified"))
      (node (ref "J7") (pin "3") (pinfunction "3_3") (pintype "unspecified"))
      (node (ref "J7") (pin "4") (pinfunction "4_4") (pintype "unspecified"))
      (node (ref "J8") (pin "2") (pinfunction "2_2") (pintype "unspecified"))
      (node (ref "J8") (pin "3") (pinfunction "3_3") (pintype "unspecified"))
      (node (ref "J8") (pin "4") (pinfunction "4_4") (pintype "unspecified"))
      (node (ref "J9") (pin "2") (pinfunction "2_2") (pintype "unspecified"))
      (node (ref "J9") (pin "3") (pinfunction "3_3") (pintype "unspecified"))
      (node (ref "J9") (pin "4") (pinfunction "4_4") (pintype "unspecified"))
      (node (ref "R22") (pin "1") (pinfunction "~_1") (pintype "unspecified"))
      (node (ref "R24") (pin "2") (pinfunction "~_2") (pintype "unspecified"))
      (node (ref "R48") (pin "1") (pinfunction "~_1") (pintype "unspecified"))
      (node (ref "R50") (pin "2") (pinfunction "~_2") (pintype "unspecified"))
      (node (ref "R52") (pin "1") (pinfunction "~_1") (pintype "unspecified"))
      (node (ref "R54") (pin "2") (pinfunction "~_2") (pintype "unspecified"))
      (node (ref "R56") (pin "1") (pinfunction "~_1") (pintype "unspecified"))
      (node (ref "R58") (pin "2") (pinfunction "~_2") (pintype "unspecified"))
      (node (ref "R60") (pin "1") (pinfunction "~_1") (pintype "unspecified"))
      (node (ref "R62") (pin "2") (pinfunction "~_2") (pintype "unspecified"))
      (node (ref "R64") (pin "1") (pinfunction "~_1") (pintype "unspecified"))
      (node (ref "R66") (pin "2") (pinfunction "~_2") (pintype "unspecified"))
      (node (ref "ROW_MUX") (pin "12") (pinfunction "GND_12") (pintype "unspecified"))
      (node (ref "ROW_MUX") (pin "15") (pinfunction "~{E}_15") (pintype "input"))
      (node (ref "ROW_MUX") (pin "16") (pinfunction "I15_16") (pintype "unspecified"))
      (node (ref "ROW_MUX") (pin "17") (pinfunction "I14_17") (pintype "unspecified"))
      (node (ref "ROW_MUX") (pin "18") (pinfunction "I13_18") (pintype "unspecified"))
      (node (ref "ROW_MUX") (pin "19") (pinfunction "I12_19") (pintype "unspecified"))
      (node (ref "ROW_MUX") (pin "20") (pinfunction "I11_20") (pintype "unspecified"))
      (node (ref "ROW_MUX") (pin "21") (pinfunction "I10_21") (pintype "unspecified"))
      (node (ref "ROW_MUX") (pin "22") (pinfunction "I9_22") (pintype "unspecified"))
      (node (ref "ROW_MUX") (pin "23") (pinfunction "I8_23") (pintype "unspecified"))
      (node (ref "RV1") (pin "3") (pinfunction "3_3") (pintype "unspecified"))
      (node (ref "RV1") (pin "4") (pinfunction "EH_4") (pintype "unspecified"))
      (node (ref "RV1") (pin "5") (pinfunction "EH_5") (pintype "unspecified"))
      (node (ref "RV2") (pin "3") (pinfunction "3_3") (pintype "unspecified"))
      (node (ref "RV2") (pin "4") (pinfunction "EH_4") (pintype "unspecified"))
      (node (ref "RV2") (pin "5") (pinfunction "EH_5") (pintype "unspecified"))
      (node (ref "RV3") (pin "3") (pinfunction "3_3") (pintype "unspecified"))
      (node (ref "RV3") (pin "4") (pinfunction "EH_4") (pintype "unspecified"))
      (node (ref "RV3") (pin "5") (pinfunction "EH_5") (pintype "unspecified"))
      (node (ref "SW49") (pin "1") (pinfunction "1_1") (pintype "unspecified"))
      (node (ref "SW49") (pin "3") (pinfunction "3_3") (pintype "unspecified"))
      (node (ref "Screen") (pin "1") (pinfunction "Pin_1_1") (pintype "unspecified"))
      (node (ref "U1") (pin "G1") (pinfunction "G1_G1") (pintype "unspecified"))
      (node (ref "U1") (pin "G3") (pinfunction "G3_G3") (pintype "unspecified"))
      (node (ref "U5") (pin "5") (pinfunction "GND_5") (pintype "unspecified"))
      (node (ref "U5") (pin "8") (pinfunction "VCC_8") (pintype "unspecified"))
      (node (ref "U8") (pin "1") (pinfunction "#1OE_1") (pintype "unspecified"))
      (node (ref "U8") (pin "10") (pinfunction "#3OE_10") (pintype "unspecified"))
      (node (ref "U8") (pin "11") (pinfunction "4Y_11") (pintype "unspecified"))
      (node (ref "U8") (pin "12") (pinfunction "4A_12") (pintype "unspecified"))
      (node (ref "U8") (pin "13") (pinfunction "#4OE_13") (pintype "unspecified"))
      (node (ref "U8") (pin "4") (pinfunction "#2OE_4") (pintype "unspecified"))
      (node (ref "U8") (pin "7") (pinfunction "GND_7") (pintype "unspecified"))
      (node (ref "U8") (pin "8") (pinfunction "3Y_8") (pintype "unspecified"))
      (node (ref "U8") (pin "9") (pinfunction "3A_9") (pintype "unspecified"))
    )
    (net (code "24") (name "LED") (class "Default")
      (node (ref "U1") (pin "6") (pinfunction "6_6") (pintype "bidirectional"))
      (node (ref "U8") (pin "2") (pinfunction "1A_2") (pintype "unspecified"))
    )
    (net (code "25") (name "LEDCNTRL") (class "Default")
      (node (ref "D1") (pin "4") (pinfunction "DIN_4") (pintype "input"))
      (node (ref "R20") (pin "2") (pinfunction "~_2") (pintype "unspecified"))
    )
    (net (code "26") (name "MAIN") (class "Default")
      (node (ref "COL_MUX") (pin "18") (pinfunction "I13_18") (pintype "unspecified"))
      (node (ref "RV3") (pin "2") (pinfunction "2_2") (pintype "unspecified"))
    )
    (net (code "27") (name "MIDI_OUT") (class "Default")
      (node (ref "R19") (pin "2") (pinfunction "~_2") (pintype "unspecified"))
      (node (ref "U8") (pin "6") (pinfunction "2Y_6") (pintype "unspecified"))
    )
    (net (code "28") (name "MIDI_RX") (class "Default")
      (node (ref "R2") (pin "2") (pinfunction "~_2") (pintype "unspecified"))
      (node (ref "U1") (pin "0") (pinfunction "0_0") (pintype "bidirectional"))
      (node (ref "U5") (pin "6") (pinfunction "VO2_6") (pintype "unspecified"))
    )
    (net (code "29") (name "MIDI_TX") (class "Default")
      (node (ref "U1") (pin "1") (pinfunction "1_1") (pintype "bidirectional"))
      (node (ref "U8") (pin "5") (pinfunction "2A_5") (pintype "unspecified"))
    )
    (net (code "30") (name "MRC") (class "Default")
      (node (ref "COL_MUX") (pin "1") (pinfunction "COM_1") (pintype "unspecified"))
      (node (ref "U1") (pin "7") (pinfunction "7_7") (pintype "bidirectional"))
    )
    (net (code "31") (name "MRR") (class "Default")
      (node (ref "ROW_MUX") (pin "1") (pinfunction "COM_1") (pintype "unspecified"))
      (node (ref "U1") (pin "22") (pinfunction "22_22") (pintype "bidirectional"))
    )
    (net (code "32") (name "MUXC1") (class "Default")
      (node (ref "COL_MUX") (pin "10") (pinfunction "S0_10") (pintype "input"))
      (node (ref "U1") (pin "8") (pinfunction "8_8") (pintype "bidirectional"))
    )
    (net (code "33") (name "MUXC2") (class "Default")
      (node (ref "COL_MUX") (pin "11") (pinfunction "S1_11") (pintype "input"))
      (node (ref "U1") (pin "9") (pinfunction "9_9") (pintype "bidirectional"))
    )
    (net (code "34") (name "MUXC3") (class "Default")
      (node (ref "COL_MUX") (pin "14") (pinfunction "S2_14") (pintype "input"))
      (node (ref "U1") (pin "10") (pinfunction "10_10") (pintype "bidirectional"))
    )
    (net (code "35") (name "MUXC4") (class "Default")
      (node (ref "COL_MUX") (pin "13") (pinfunction "S3_13") (pintype "input"))
      (node (ref "U1") (pin "11") (pinfunction "11_11") (pintype "bidirectional"))
    )
    (net (code "36") (name "MUXR1") (class "Default")
      (node (ref "ROW_MUX") (pin "10") (pinfunction "S0_10") (pintype "input"))
      (node (ref "U1") (pin "2") (pinfunction "2_2") (pintype "bidirectional"))
    )
    (net (code "37") (name "MUXR2") (class "Default")
      (node (ref "ROW_MUX") (pin "11") (pinfunction "S1_11") (pintype "input"))
      (node (ref "U1") (pin "3") (pinfunction "3_3") (pintype "bidirectional"))
    )
    (net (code "38") (name "MUXR3") (class "Default")
      (node (ref "ROW_MUX") (pin "14") (pinfunction "S2_14") (pintype "input"))
      (node (ref "U1") (pin "4") (pinfunction "4_4") (pintype "bidirectional"))
    )
    (net (code "39") (name "MUXR4") (class "Default")
      (node (ref "ROW_MUX") (pin "13") (pinfunction "S3_13") (pintype "input"))
      (node (ref "U1") (pin "5") (pinfunction "5_5") (pintype "bidirectional"))
    )
    (net (code "40") (name "Net-(C11-Pad1)") (class "Default")
      (node (ref "C11") (pin "1") (pinfunction "1_1") (pintype "input"))
      (node (ref "J4") (pin "1") (pinfunction "1_1") (pintype "unspecified"))
    )
    (net (code "41") (name "Net-(C11-Pad2)") (class "Default")
      (node (ref "C11") (pin "2") (pinfunction "2_2") (pintype "input"))
      (node (ref "R22") (pin "2") (pinfunction "~_2") (pintype "unspecified"))
      (node (ref "R23") (pin "2") (pinfunction "~_2") (pintype "unspecified"))
    )
    (net (code "42") (name "Net-(C37-~-Pad1)") (class "Default")
      (node (ref "C37") (pin "1") (pinfunction "~_1") (pintype "unspecified"))
      (node (ref "C38") (pin "1") (pinfunction "1_1") (pintype "input"))
      (node (ref "R46") (pin "1") (pinfunction "~_1") (pintype "unspecified"))
      (node (ref "U1") (pin "G2") (pinfunction "G2_G2") (pintype "unspecified"))
    )
    (net (code "43") (name "Net-(C37-~-Pad2)") (class "Default")
      (node (ref "C37") (pin "2") (pinfunction "~_2") (pintype "unspecified"))
      (node (ref "C38") (pin "2") (pinfunction "2_2") (pintype "input"))
      (node (ref "R47") (pin "1") (pinfunction "~_1") (pintype "unspecified"))
      (node (ref "U1") (pin "3.3V_1") (pinfunction "3.3V_1_3.3V_1") (pintype "unspecified"))
    )
    (net (code "44") (name "Net-(C39-Pad1)") (class "Default")
      (node (ref "C39") (pin "1") (pinfunction "1_1") (pintype "input"))
      (node (ref "J5") (pin "1") (pinfunction "1_1") (pintype "unspecified"))
    )
    (net (code "45") (name "Net-(C39-Pad2)") (class "Default")
      (node (ref "C39") (pin "2") (pinfunction "2_2") (pintype "input"))
      (node (ref "R48") (pin "2") (pinfunction "~_2") (pintype "unspecified"))
      (node (ref "R49") (pin "2") (pinfunction "~_2") (pintype "unspecified"))
    )
    (net (code "46") (name "Net-(C42-Pad1)") (class "Default")
      (node (ref "C42") (pin "1") (pinfunction "1_1") (pintype "input"))
      (node (ref "J6") (pin "1") (pinfunction "1_1") (pintype "unspecified"))
    )
    (net (code "47") (name "Net-(C42-Pad2)") (class "Default")
      (node (ref "C42") (pin "2") (pinfunction "2_2") (pintype "input"))
      (node (ref "R52") (pin "2") (pinfunction "~_2") (pintype "unspecified"))
      (node (ref "R53") (pin "2") (pinfunction "~_2") (pintype "unspecified"))
    )
    (net (code "48") (name "Net-(C45-Pad1)") (class "Default")
      (node (ref "C45") (pin "1") (pinfunction "1_1") (pintype "input"))
      (node (ref "J7") (pin "1") (pinfunction "1_1") (pintype "unspecified"))
    )
    (net (code "49") (name "Net-(C45-Pad2)") (class "Default")
      (node (ref "C45") (pin "2") (pinfunction "2_2") (pintype "input"))
      (node (ref "R56") (pin "2") (pinfunction "~_2") (pintype "unspecified"))
      (node (ref "R57") (pin "2") (pinfunction "~_2") (pintype "unspecified"))
    )
    (net (code "50") (name "Net-(C48-Pad1)") (class "Default")
      (node (ref "C48") (pin "1") (pinfunction "1_1") (pintype "input"))
      (node (ref "J8") (pin "1") (pinfunction "1_1") (pintype "unspecified"))
    )
    (net (code "51") (name "Net-(C48-Pad2)") (class "Default")
      (node (ref "C48") (pin "2") (pinfunction "2_2") (pintype "input"))
      (node (ref "R60") (pin "2") (pinfunction "~_2") (pintype "unspecified"))
      (node (ref "R61") (pin "2") (pinfunction "~_2") (pintype "unspecified"))
    )
    (net (code "52") (name "Net-(C51-Pad1)") (class "Default")
      (node (ref "C51") (pin "1") (pinfunction "1_1") (pintype "input"))
      (node (ref "J9") (pin "1") (pinfunction "1_1") (pintype "unspecified"))
    )
    (net (code "53") (name "Net-(C51-Pad2)") (class "Default")
      (node (ref "C51") (pin "2") (pinfunction "2_2") (pintype "input"))
      (node (ref "R64") (pin "2") (pinfunction "~_2") (pintype "unspecified"))
      (node (ref "R65") (pin "2") (pinfunction "~_2") (pintype "unspecified"))
    )
    (net (code "54") (name "Net-(D1-DOUT)") (class "Default")
      (node (ref "D1") (pin "2") (pinfunction "DOUT_2") (pintype "output"))
      (node (ref "D2") (pin "4") (pinfunction "DIN_4") (pintype "input"))
    )
    (net (code "55") (name "Net-(D1-VSS)") (class "Default")
      (node (ref "D1") (pin "3") (pinfunction "VSS_3") (pintype "unspecified"))
      (node (ref "D2") (pin "1") (pinfunction "VDD_1") (pintype "unspecified"))
    )
    (net (code "56") (name "Net-(D2-DOUT)") (class "Default")
      (node (ref "D2") (pin "2") (pinfunction "DOUT_2") (pintype "output"))
      (node (ref "D3") (pin "4") (pinfunction "DIN_4") (pintype "input"))
    )
    (net (code "57") (name "Net-(D2-VSS)") (class "Default")
      (node (ref "D2") (pin "3") (pinfunction "VSS_3") (pintype "unspecified"))
      (node (ref "D3") (pin "1") (pinfunction "VDD_1") (pintype "unspecified"))
    )
    (net (code "58") (name "Net-(D3-DOUT)") (class "Default")
      (node (ref "D3") (pin "2") (pinfunction "DOUT_2") (pintype "output"))
      (node (ref "D4") (pin "4") (pinfunction "DIN_4") (pintype "input"))
    )
    (net (code "59") (name "Net-(D3-VSS)") (class "Default")
      (node (ref "D3") (pin "3") (pinfunction "VSS_3") (pintype "unspecified"))
      (node (ref "D4") (pin "1") (pinfunction "VDD_1") (pintype "unspecified"))
    )
    (net (code "60") (name "Net-(D4-DOUT)") (class "Default")
      (node (ref "D4") (pin "2") (pinfunction "DOUT_2") (pintype "output"))
      (node (ref "D5") (pin "4") (pinfunction "DIN_4") (pintype "input"))
    )
    (net (code "61") (name "Net-(D4-VSS)") (class "Default")
      (node (ref "D4") (pin "3") (pinfunction "VSS_3") (pintype "unspecified"))
      (node (ref "D5") (pin "1") (pinfunction "VDD_1") (pintype "unspecified"))
    )
    (net (code "62") (name "Net-(D5-DOUT)") (class "Default")
      (node (ref "D5") (pin "2") (pinfunction "DOUT_2") (pintype "output"))
      (node (ref "D6") (pin "4") (pinfunction "DIN_4") (pintype "input"))
    )
    (net (code "63") (name "Net-(D5-VSS)") (class "Default")
      (node (ref "D5") (pin "3") (pinfunction "VSS_3") (pintype "unspecified"))
      (node (ref "D6") (pin "1") (pinfunction "VDD_1") (pintype "unspecified"))
    )
    (net (code "64") (name "Net-(D6-DOUT)") (class "Default")
      (node (ref "D6") (pin "2") (pinfunction "DOUT_2") (pintype "output"))
      (node (ref "D7") (pin "4") (pinfunction "DIN_4") (pintype "input"))
    )
    (net (code "65") (name "Net-(D6-VSS)") (class "Default")
      (node (ref "C31") (pin "1") (pinfunction "~_1") (pintype "unspecified"))
      (node (ref "D6") (pin "3") (pinfunction "VSS_3") (pintype "unspecified"))
      (node (ref "D7") (pin "1") (pinfunction "VDD_1") (pintype "unspecified"))
    )
    (net (code "66") (name "Net-(D7-DOUT)") (class "Default")
      (node (ref "D7") (pin "2") (pinfunction "DOUT_2") (pintype "output"))
      (node (ref "D8") (pin "4") (pinfunction "DIN_4") (pintype "input"))
    )
    (net (code "67") (name "Net-(D7-VSS)") (class "Default")
      (node (ref "D7") (pin "3") (pinfunction "VSS_3") (pintype "unspecified"))
      (node (ref "D8") (pin "1") (pinfunction "VDD_1") (pintype "unspecified"))
    )
    (net (code "68") (name "Net-(D8-DOUT)") (class "Default")
      (node (ref "D8") (pin "2") (pinfunction "DOUT_2") (pintype "output"))
      (node (ref "D9") (pin "4") (pinfunction "DIN_4") (pintype "input"))
    )
    (net (code "69") (name "Net-(D8-VSS)") (class "Default")
      (node (ref "D8") (pin "3") (pinfunction "VSS_3") (pintype "unspecified"))
      (node (ref "D9") (pin "1") (pinfunction "VDD_1") (pintype "unspecified"))
    )
    (net (code "70") (name "Net-(D10-DIN)") (class "Default")
      (node (ref "D10") (pin "4") (pinfunction "DIN_4") (pintype "input"))
      (node (ref "D9") (pin "2") (pinfunction "DOUT_2") (pintype "output"))
    )
    (net (code "71") (name "Net-(D10-DOUT)") (class "Default")
      (node (ref "D10") (pin "2") (pinfunction "DOUT_2") (pintype "output"))
      (node (ref "D11") (pin "4") (pinfunction "DIN_4") (pintype "input"))
    )
    (net (code "72") (name "Net-(D10-VDD)") (class "Default")
      (node (ref "D10") (pin "1") (pinfunction "VDD_1") (pintype "unspecified"))
      (node (ref "D9") (pin "3") (pinfunction "VSS_3") (pintype "unspecified"))
    )
    (net (code "73") (name "Net-(D10-VSS)") (class "Default")
      (node (ref "D10") (pin "3") (pinfunction "VSS_3") (pintype "unspecified"))
      (node (ref "D11") (pin "1") (pinfunction "VDD_1") (pintype "unspecified"))
    )
    (net (code "74") (name "Net-(D11-DOUT)") (class "Default")
      (node (ref "D11") (pin "2") (pinfunction "DOUT_2") (pintype "output"))
      (node (ref "D12") (pin "4") (pinfunction "DIN_4") (pintype "input"))
    )
    (net (code "75") (name "Net-(D11-VSS)") (class "Default")
      (node (ref "D11") (pin "3") (pinfunction "VSS_3") (pintype "unspecified"))
      (node (ref "D12") (pin "1") (pinfunction "VDD_1") (pintype "unspecified"))
    )
    (net (code "76") (name "Net-(D12-DOUT)") (class "Default")
      (node (ref "D12") (pin "2") (pinfunction "DOUT_2") (pintype "output"))
      (node (ref "D13") (pin "4") (pinfunction "DIN_4") (pintype "input"))
    )
    (net (code "77") (name "Net-(D12-VSS)") (class "Default")
      (node (ref "C32") (pin "1") (pinfunction "~_1") (pintype "unspecified"))
      (node (ref "D12") (pin "3") (pinfunction "VSS_3") (pintype "unspecified"))
      (node (ref "D13") (pin "1") (pinfunction "VDD_1") (pintype "unspecified"))
    )
    (net (code "78") (name "Net-(D13-DOUT)") (class "Default")
      (node (ref "D13") (pin "2") (pinfunction "DOUT_2") (pintype "output"))
      (node (ref "D14") (pin "4") (pinfunction "DIN_4") (pintype "input"))
    )
    (net (code "79") (name "Net-(D13-VSS)") (class "Default")
      (node (ref "D13") (pin "3") (pinfunction "VSS_3") (pintype "unspecified"))
      (node (ref "D14") (pin "1") (pinfunction "VDD_1") (pintype "unspecified"))
    )
    (net (code "80") (name "Net-(D14-DOUT)") (class "Default")
      (node (ref "D14") (pin "2") (pinfunction "DOUT_2") (pintype "output"))
      (node (ref "D15") (pin "4") (pinfunction "DIN_4") (pintype "input"))
    )
    (net (code "81") (name "Net-(D14-VSS)") (class "Default")
      (node (ref "D14") (pin "3") (pinfunction "VSS_3") (pintype "unspecified"))
      (node (ref "D15") (pin "1") (pinfunction "VDD_1") (pintype "unspecified"))
    )
    (net (code "82") (name "Net-(D15-DOUT)") (class "Default")
      (node (ref "D15") (pin "2") (pinfunction "DOUT_2") (pintype "output"))
      (node (ref "D16") (pin "4") (pinfunction "DIN_4") (pintype "input"))
    )
    (net (code "83") (name "Net-(D15-VSS)") (class "Default")
      (node (ref "D15") (pin "3") (pinfunction "VSS_3") (pintype "unspecified"))
      (node (ref "D16") (pin "1") (pinfunction "VDD_1") (pintype "unspecified"))
    )
    (net (code "84") (name "Net-(D16-DOUT)") (class "Default")
      (node (ref "D16") (pin "2") (pinfunction "DOUT_2") (pintype "output"))
      (node (ref "D17") (pin "4") (pinfunction "DIN_4") (pintype "input"))
    )
    (net (code "85") (name "Net-(D16-VSS)") (class "Default")
      (node (ref "D16") (pin "3") (pinfunction "VSS_3") (pintype "unspecified"))
      (node (ref "D17") (pin "1") (pinfunction "VDD_1") (pintype "unspecified"))
    )
    (net (code "86") (name "Net-(D17-DOUT)") (class "Default")
      (node (ref "D17") (pin "2") (pinfunction "DOUT_2") (pintype "output"))
      (node (ref "D18") (pin "4") (pinfunction "DIN_4") (pintype "input"))
    )
    (net (code "87") (name "Net-(D17-VSS)") (class "Default")
      (node (ref "D17") (pin "3") (pinfunction "VSS_3") (pintype "unspecified"))
      (node (ref "D18") (pin "1") (pinfunction "VDD_1") (pintype "unspecified"))
    )
    (net (code "88") (name "Net-(D18-DOUT)") (class "Default")
      (node (ref "D18") (pin "2") (pinfunction "DOUT_2") (pintype "output"))
      (node (ref "D19") (pin "4") (pinfunction "DIN_4") (pintype "input"))
    )
    (net (code "89") (name "Net-(D18-VSS)") (class "Default")
      (node (ref "C33") (pin "1") (pinfunction "~_1") (pintype "unspecified"))
      (node (ref "D18") (pin "3") (pinfunction "VSS_3") (pintype "unspecified"))
      (node (ref "D19") (pin "1") (pinfunction "VDD_1") (pintype "unspecified"))
    )
    (net (code "90") (name "Net-(D19-DOUT)") (class "Default")
      (node (ref "D19") (pin "2") (pinfunction "DOUT_2") (pintype "output"))
      (node (ref "D20") (pin "4") (pinfunction "DIN_4") (pintype "input"))
    )
    (net (code "91") (name "Net-(D19-VSS)") (class "Default")
      (node (ref "D19") (pin "3") (pinfunction "VSS_3") (pintype "unspecified"))
      (node (ref "D20") (pin "1") (pinfunction "VDD_1") (pintype "unspecified"))
    )
    (net (code "92") (name "Net-(D20-DOUT)") (class "Default")
      (node (ref "D20") (pin "2") (pinfunction "DOUT_2") (pintype "output"))
      (node (ref "D21") (pin "4") (pinfunction "DIN_4") (pintype "input"))
    )
    (net (code "93") (name "Net-(D20-VSS)") (class "Default")
      (node (ref "D20") (pin "3") (pinfunction "VSS_3") (pintype "unspecified"))
      (node (ref "D21") (pin "1") (pinfunction "VDD_1") (pintype "unspecified"))
    )
    (net (code "94") (name "Net-(D21-DOUT)") (class "Default")
      (node (ref "D21") (pin "2") (pinfunction "DOUT_2") (pintype "output"))
      (node (ref "D22") (pin "4") (pinfunction "DIN_4") (pintype "input"))
    )
    (net (code "95") (name "Net-(D21-VSS)") (class "Default")
      (node (ref "D21") (pin "3") (pinfunction "VSS_3") (pintype "unspecified"))
      (node (ref "D22") (pin "1") (pinfunction "VDD_1") (pintype "unspecified"))
    )
    (net (code "96") (name "Net-(D22-DOUT)") (class "Default")
      (node (ref "D22") (pin "2") (pinfunction "DOUT_2") (pintype "output"))
      (node (ref "D23") (pin "4") (pinfunction "DIN_4") (pintype "input"))
    )
    (net (code "97") (name "Net-(D22-VSS)") (class "Default")
      (node (ref "D22") (pin "3") (pinfunction "VSS_3") (pintype "unspecified"))
      (node (ref "D23") (pin "1") (pinfunction "VDD_1") (pintype "unspecified"))
    )
    (net (code "98") (name "Net-(D23-DOUT)") (class "Default")
      (node (ref "D23") (pin "2") (pinfunction "DOUT_2") (pintype "output"))
      (node (ref "D24") (pin "4") (pinfunction "DIN_4") (pintype "input"))
    )
    (net (code "99") (name "Net-(D23-VSS)") (class "Default")
      (node (ref "D23") (pin "3") (pinfunction "VSS_3") (pintype "unspecified"))
      (node (ref "D24") (pin "1") (pinfunction "VDD_1") (pintype "unspecified"))
    )
    (net (code "100") (name "Net-(D24-DOUT)") (class "Default")
      (node (ref "D24") (pin "2") (pinfunction "DOUT_2") (pintype "output"))
      (node (ref "D25") (pin "4") (pinfunction "DIN_4") (pintype "input"))
    )
    (net (code "101") (name "Net-(D24-VSS)") (class "Default")
      (node (ref "C34") (pin "1") (pinfunction "~_1") (pintype "unspecified"))
      (node (ref "D24") (pin "3") (pinfunction "VSS_3") (pintype "unspecified"))
      (node (ref "D25") (pin "1") (pinfunction "VDD_1") (pintype "unspecified"))
    )
    (net (code "102") (name "Net-(D25-DOUT)") (class "Default")
      (node (ref "D25") (pin "2") (pinfunction "DOUT_2") (pintype "output"))
      (node (ref "D26") (pin "4") (pinfunction "DIN_4") (pintype "input"))
    )
    (net (code "103") (name "Net-(D25-VSS)") (class "Default")
      (node (ref "D25") (pin "3") (pinfunction "VSS_3") (pintype "unspecified"))
      (node (ref "D26") (pin "1") (pinfunction "VDD_1") (pintype "unspecified"))
    )
    (net (code "104") (name "Net-(D26-DOUT)") (class "Default")
      (node (ref "D26") (pin "2") (pinfunction "DOUT_2") (pintype "output"))
      (node (ref "D27") (pin "4") (pinfunction "DIN_4") (pintype "input"))
    )
    (net (code "105") (name "Net-(D26-VSS)") (class "Default")
      (node (ref "D26") (pin "3") (pinfunction "VSS_3") (pintype "unspecified"))
      (node (ref "D27") (pin "1") (pinfunction "VDD_1") (pintype "unspecified"))
    )
    (net (code "106") (name "Net-(D27-DOUT)") (class "Default")
      (node (ref "D27") (pin "2") (pinfunction "DOUT_2") (pintype "output"))
      (node (ref "D28") (pin "4") (pinfunction "DIN_4") (pintype "input"))
    )
    (net (code "107") (name "Net-(D27-VSS)") (class "Default")
      (node (ref "D27") (pin "3") (pinfunction "VSS_3") (pintype "unspecified"))
      (node (ref "D28") (pin "1") (pinfunction "VDD_1") (pintype "unspecified"))
    )
    (net (code "108") (name "Net-(D28-DOUT)") (class "Default")
      (node (ref "D28") (pin "2") (pinfunction "DOUT_2") (pintype "output"))
      (node (ref "D29") (pin "4") (pinfunction "DIN_4") (pintype "input"))
    )
    (net (code "109") (name "Net-(D28-VSS)") (class "Default")
      (node (ref "D28") (pin "3") (pinfunction "VSS_3") (pintype "unspecified"))
      (node (ref "D29") (pin "1") (pinfunction "VDD_1") (pintype "unspecified"))
    )
    (net (code "110") (name "Net-(D29-DOUT)") (class "Default")
      (node (ref "D29") (pin "2") (pinfunction "DOUT_2") (pintype "output"))
      (node (ref "D30") (pin "4") (pinfunction "DIN_4") (pintype "input"))
    )
    (net (code "111") (name "Net-(D29-VSS)") (class "Default")
      (node (ref "D29") (pin "3") (pinfunction "VSS_3") (pintype "unspecified"))
      (node (ref "D30") (pin "1") (pinfunction "VDD_1") (pintype "unspecified"))
    )
    (net (code "112") (name "Net-(D30-DOUT)") (class "Default")
      (node (ref "D30") (pin "2") (pinfunction "DOUT_2") (pintype "output"))
      (node (ref "D31") (pin "4") (pinfunction "DIN_4") (pintype "input"))
    )
    (net (code "113") (name "Net-(D30-VSS)") (class "Default")
      (node (ref "C35") (pin "1") (pinfunction "~_1") (pintype "unspecified"))
      (node (ref "D30") (pin "3") (pinfunction "VSS_3") (pintype "unspecified"))
      (node (ref "D31") (pin "1") (pinfunction "VDD_1") (pintype "unspecified"))
    )
    (net (code "114") (name "Net-(D31-DOUT)") (class "Default")
      (node (ref "D31") (pin "2") (pinfunction "DOUT_2") (pintype "output"))
      (node (ref "D32") (pin "4") (pinfunction "DIN_4") (pintype "input"))
    )
    (net (code "115") (name "Net-(D31-VSS)") (class "Default")
      (node (ref "D31") (pin "3") (pinfunction "VSS_3") (pintype "unspecified"))
      (node (ref "D32") (pin "1") (pinfunction "VDD_1") (pintype "unspecified"))
    )
    (net (code "116") (name "Net-(D32-DOUT)") (class "Default")
      (node (ref "D32") (pin "2") (pinfunction "DOUT_2") (pintype "output"))
      (node (ref "D33") (pin "4") (pinfunction "DIN_4") (pintype "input"))
    )
    (net (code "117") (name "Net-(D32-VSS)") (class "Default")
      (node (ref "D32") (pin "3") (pinfunction "VSS_3") (pintype "unspecified"))
      (node (ref "D33") (pin "1") (pinfunction "VDD_1") (pintype "unspecified"))
    )
    (net (code "118") (name "Net-(D33-DOUT)") (class "Default")
      (node (ref "D33") (pin "2") (pinfunction "DOUT_2") (pintype "output"))
      (node (ref "D34") (pin "4") (pinfunction "DIN_4") (pintype "input"))
    )
    (net (code "119") (name "Net-(D33-VSS)") (class "Default")
      (node (ref "D33") (pin "3") (pinfunction "VSS_3") (pintype "unspecified"))
      (node (ref "D34") (pin "1") (pinfunction "VDD_1") (pintype "unspecified"))
    )
    (net (code "120") (name "Net-(D34-DOUT)") (class "Default")
      (node (ref "D34") (pin "2") (pinfunction "DOUT_2") (pintype "output"))
      (node (ref "D35") (pin "4") (pinfunction "DIN_4") (pintype "input"))
    )
    (net (code "121") (name "Net-(D34-VSS)") (class "Default")
      (node (ref "D34") (pin "3") (pinfunction "VSS_3") (pintype "unspecified"))
      (node (ref "D35") (pin "1") (pinfunction "VDD_1") (pintype "unspecified"))
    )
    (net (code "122") (name "Net-(D35-DOUT)") (class "Default")
      (node (ref "D35") (pin "2") (pinfunction "DOUT_2") (pintype "output"))
      (node (ref "D36") (pin "4") (pinfunction "DIN_4") (pintype "input"))
    )
    (net (code "123") (name "Net-(D35-VSS)") (class "Default")
      (node (ref "D35") (pin "3") (pinfunction "VSS_3") (pintype "unspecified"))
      (node (ref "D36") (pin "1") (pinfunction "VDD_1") (pintype "unspecified"))
    )
    (net (code "124") (name "Net-(D36-DOUT)") (class "Default")
      (node (ref "D36") (pin "2") (pinfunction "DOUT_2") (pintype "output"))
      (node (ref "D37") (pin "4") (pinfunction "DIN_4") (pintype "input"))
    )
    (net (code "125") (name "Net-(D36-VSS)") (class "Default")
      (node (ref "C36") (pin "1") (pinfunction "~_1") (pintype "unspecified"))
      (node (ref "D36") (pin "3") (pinfunction "VSS_3") (pintype "unspecified"))
      (node (ref "D37") (pin "1") (pinfunction "VDD_1") (pintype "unspecified"))
    )
    (net (code "126") (name "Net-(D37-DOUT)") (class "Default")
      (node (ref "D37") (pin "2") (pinfunction "DOUT_2") (pintype "output"))
      (node (ref "D38") (pin "4") (pinfunction "DIN_4") (pintype "input"))
    )
    (net (code "127") (name "Net-(D37-VSS)") (class "Default")
      (node (ref "D37") (pin "3") (pinfunction "VSS_3") (pintype "unspecified"))
      (node (ref "D38") (pin "1") (pinfunction "VDD_1") (pintype "unspecified"))
    )
    (net (code "128") (name "Net-(D38-DOUT)") (class "Default")
      (node (ref "D38") (pin "2") (pinfunction "DOUT_2") (pintype "output"))
      (node (ref "D39") (pin "4") (pinfunction "DIN_4") (pintype "input"))
    )
    (net (code "129") (name "Net-(D38-VSS)") (class "Default")
      (node (ref "D38") (pin "3") (pinfunction "VSS_3") (pintype "unspecified"))
      (node (ref "D39") (pin "1") (pinfunction "VDD_1") (pintype "unspecified"))
    )
    (net (code "130") (name "Net-(D39-DOUT)") (class "Default")
      (node (ref "D39") (pin "2") (pinfunction "DOUT_2") (pintype "output"))
      (node (ref "D40") (pin "4") (pinfunction "DIN_4") (pintype "input"))
    )
    (net (code "131") (name "Net-(D39-VSS)") (class "Default")
      (node (ref "D39") (pin "3") (pinfunction "VSS_3") (pintype "unspecified"))
      (node (ref "D40") (pin "1") (pinfunction "VDD_1") (pintype "unspecified"))
    )
    (net (code "132") (name "Net-(D40-DOUT)") (class "Default")
      (node (ref "D40") (pin "2") (pinfunction "DOUT_2") (pintype "output"))
      (node (ref "D41") (pin "4") (pinfunction "DIN_4") (pintype "input"))
    )
    (net (code "133") (name "Net-(D40-VSS)") (class "Default")
      (node (ref "D40") (pin "3") (pinfunction "VSS_3") (pintype "unspecified"))
      (node (ref "D41") (pin "1") (pinfunction "VDD_1") (pintype "unspecified"))
    )
    (net (code "134") (name "Net-(D41-DOUT)") (class "Default")
      (node (ref "D41") (pin "2") (pinfunction "DOUT_2") (pintype "output"))
      (node (ref "D42") (pin "4") (pinfunction "DIN_4") (pintype "input"))
    )
    (net (code "135") (name "Net-(D41-VSS)") (class "Default")
      (node (ref "D41") (pin "3") (pinfunction "VSS_3") (pintype "unspecified"))
      (node (ref "D42") (pin "1") (pinfunction "VDD_1") (pintype "unspecified"))
    )
    (net (code "136") (name "Net-(D43-A)") (class "Default")
      (node (ref "D43") (pin "2") (pinfunction "A_2") (pintype "unspecified"))
      (node (ref "R21") (pin "1") (pinfunction "~_1") (pintype "unspecified"))
      (node (ref "U5") (pin "3") (pinfunction "C2_3") (pintype "unspecified"))
    )
    (net (code "137") (name "Net-(D43-K)") (class "Default")
      (node (ref "D43") (pin "1") (pinfunction "K_1") (pintype "unspecified"))
      (node (ref "J2") (pin "4") (pinfunction "4_4") (pintype "unspecified"))
      (node (ref "U5") (pin "2") (pinfunction "C1_2") (pintype "unspecified"))
    )
    (net (code "138") (name "Net-(D45-A)") (class "Default")
      (node (ref "D45") (pin "2") (pinfunction "A_2") (pintype "unspecified"))
      (node (ref "R24") (pin "1") (pinfunction "~_1") (pintype "unspecified"))
      (node (ref "R25") (pin "1") (pinfunction "~_1") (pintype "unspecified"))
      (node (ref "U15") (pin "1") (pinfunction "OUTA_1") (pintype "output"))
    )
    (net (code "139") (name "Net-(D45-K)") (class "Default")
      (node (ref "D45") (pin "1") (pinfunction "K_1") (pintype "unspecified"))
      (node (ref "R23") (pin "1") (pinfunction "~_1") (pintype "unspecified"))
      (node (ref "U15") (pin "2") (pinfunction "INA-_2") (pintype "unspecified"))
    )
    (net (code "140") (name "Net-(D46-A)") (class "Default")
      (node (ref "D46") (pin "2") (pinfunction "A_2") (pintype "unspecified"))
      (node (ref "R50") (pin "1") (pinfunction "~_1") (pintype "unspecified"))
      (node (ref "R51") (pin "1") (pinfunction "~_1") (pintype "unspecified"))
      (node (ref "U16") (pin "1") (pinfunction "OUTA_1") (pintype "output"))
    )
    (net (code "141") (name "Net-(D46-K)") (class "Default")
      (node (ref "D46") (pin "1") (pinfunction "K_1") (pintype "unspecified"))
      (node (ref "R49") (pin "1") (pinfunction "~_1") (pintype "unspecified"))
      (node (ref "U16") (pin "2") (pinfunction "INA-_2") (pintype "unspecified"))
    )
    (net (code "142") (name "Net-(D47-A)") (class "Default")
      (node (ref "D47") (pin "2") (pinfunction "A_2") (pintype "unspecified"))
      (node (ref "R54") (pin "1") (pinfunction "~_1") (pintype "unspecified"))
      (node (ref "R55") (pin "1") (pinfunction "~_1") (pintype "unspecified"))
      (node (ref "U17") (pin "1") (pinfunction "OUTA_1") (pintype "output"))
    )
    (net (code "143") (name "Net-(D47-K)") (class "Default")
      (node (ref "D47") (pin "1") (pinfunction "K_1") (pintype "unspecified"))
      (node (ref "R53") (pin "1") (pinfunction "~_1") (pintype "unspecified"))
      (node (ref "U17") (pin "2") (pinfunction "INA-_2") (pintype "unspecified"))
    )
    (net (code "144") (name "Net-(D48-A)") (class "Default")
      (node (ref "D48") (pin "2") (pinfunction "A_2") (pintype "unspecified"))
      (node (ref "R58") (pin "1") (pinfunction "~_1") (pintype "unspecified"))
      (node (ref "R59") (pin "1") (pinfunction "~_1") (pintype "unspecified"))
      (node (ref "U18") (pin "1") (pinfunction "OUTA_1") (pintype "output"))
    )
    (net (code "145") (name "Net-(D48-K)") (class "Default")
      (node (ref "D48") (pin "1") (pinfunction "K_1") (pintype "unspecified"))
      (node (ref "R57") (pin "1") (pinfunction "~_1") (pintype "unspecified"))
      (node (ref "U18") (pin "2") (pinfunction "INA-_2") (pintype "unspecified"))
    )
    (net (code "146") (name "Net-(D49-A)") (class "Default")
      (node (ref "D49") (pin "2") (pinfunction "A_2") (pintype "unspecified"))
      (node (ref "R62") (pin "1") (pinfunction "~_1") (pintype "unspecified"))
      (node (ref "R63") (pin "1") (pinfunction "~_1") (pintype "unspecified"))
      (node (ref "U19") (pin "1") (pinfunction "OUTA_1") (pintype "output"))
    )
    (net (code "147") (name "Net-(D49-K)") (class "Default")
      (node (ref "D49") (pin "1") (pinfunction "K_1") (pintype "unspecified"))
      (node (ref "R61") (pin "1") (pinfunction "~_1") (pintype "unspecified"))
      (node (ref "U19") (pin "2") (pinfunction "INA-_2") (pintype "unspecified"))
    )
    (net (code "148") (name "Net-(D50-A)") (class "Default")
      (node (ref "D50") (pin "2") (pinfunction "A_2") (pintype "unspecified"))
      (node (ref "R66") (pin "1") (pinfunction "~_1") (pintype "unspecified"))
      (node (ref "R67") (pin "1") (pinfunction "~_1") (pintype "unspecified"))
      (node (ref "U20") (pin "1") (pinfunction "OUTA_1") (pintype "output"))
    )
    (net (code "149") (name "Net-(D50-K)") (class "Default")
      (node (ref "D50") (pin "1") (pinfunction "K_1") (pintype "unspecified"))
      (node (ref "R65") (pin "1") (pinfunction "~_1") (pintype "unspecified"))
      (node (ref "U20") (pin "2") (pinfunction "INA-_2") (pintype "unspecified"))
    )
    (net (code "150") (name "Net-(J2-Pad5)") (class "Default")
      (node (ref "J2") (pin "5") (pinfunction "5_5") (pintype "unspecified"))
      (node (ref "R21") (pin "2") (pinfunction "~_2") (pintype "unspecified"))
    )
    (net (code "151") (name "Net-(J3-Pad4)") (class "Default")
      (node (ref "J3") (pin "4") (pinfunction "4_4") (pintype "unspecified"))
      (node (ref "R4") (pin "1") (pinfunction "~_1") (pintype "unspecified"))
    )
    (net (code "152") (name "Net-(J3-Pad5)") (class "Default")
      (node (ref "J3") (pin "5") (pinfunction "5_5") (pintype "unspecified"))
      (node (ref "R19") (pin "1") (pinfunction "~_1") (pintype "unspecified"))
    )
    (net (code "153") (name "Net-(U8-1Y)") (class "Default")
      (node (ref "R20") (pin "1") (pinfunction "~_1") (pintype "unspecified"))
      (node (ref "U8") (pin "3") (pinfunction "1Y_3") (pintype "unspecified"))
    )
    (net (code "154") (name "Net-(U15A-VSS)") (class "Default")
      (node (ref "C25") (pin "1") (pinfunction "1_1") (pintype "unspecified"))
      (node (ref "U15") (pin "4") (pinfunction "VSS_4") (pintype "unspecified"))
    )
    (net (code "155") (name "Net-(U16A-VDD)") (class "Default")
      (node (ref "C41") (pin "2") (pinfunction "2_2") (pintype "unspecified"))
      (node (ref "U16") (pin "8") (pinfunction "VDD_8") (pintype "unspecified"))
    )
    (net (code "156") (name "Net-(U16A-VSS)") (class "Default")
      (node (ref "C41") (pin "1") (pinfunction "1_1") (pintype "unspecified"))
      (node (ref "U16") (pin "4") (pinfunction "VSS_4") (pintype "unspecified"))
    )
    (net (code "157") (name "Net-(U17A-VDD)") (class "Default")
      (node (ref "C44") (pin "2") (pinfunction "2_2") (pintype "unspecified"))
      (node (ref "U17") (pin "8") (pinfunction "VDD_8") (pintype "unspecified"))
    )
    (net (code "158") (name "Net-(U17A-VSS)") (class "Default")
      (node (ref "C44") (pin "1") (pinfunction "1_1") (pintype "unspecified"))
      (node (ref "U17") (pin "4") (pinfunction "VSS_4") (pintype "unspecified"))
    )
    (net (code "159") (name "Net-(U18A-VDD)") (class "Default")
      (node (ref "C47") (pin "2") (pinfunction "2_2") (pintype "unspecified"))
      (node (ref "U18") (pin "8") (pinfunction "VDD_8") (pintype "unspecified"))
    )
    (net (code "160") (name "Net-(U18A-VSS)") (class "Default")
      (node (ref "C47") (pin "1") (pinfunction "1_1") (pintype "unspecified"))
      (node (ref "U18") (pin "4") (pinfunction "VSS_4") (pintype "unspecified"))
    )
    (net (code "161") (name "Net-(U19A-VDD)") (class "Default")
      (node (ref "C50") (pin "2") (pinfunction "2_2") (pintype "unspecified"))
      (node (ref "U19") (pin "8") (pinfunction "VDD_8") (pintype "unspecified"))
    )
    (net (code "162") (name "Net-(U19A-VSS)") (class "Default")
      (node (ref "C50") (pin "1") (pinfunction "1_1") (pintype "unspecified"))
      (node (ref "U19") (pin "4") (pinfunction "VSS_4") (pintype "unspecified"))
    )
    (net (code "163") (name "Net-(U20A-VDD)") (class "Default")
      (node (ref "C53") (pin "2") (pinfunction "2_2") (pintype "unspecified"))
      (node (ref "U20") (pin "8") (pinfunction "VDD_8") (pintype "unspecified"))
    )
    (net (code "164") (name "Net-(U20A-VSS)") (class "Default")
      (node (ref "C53") (pin "1") (pinfunction "1_1") (pintype "unspecified"))
      (node (ref "U20") (pin "4") (pinfunction "VSS_4") (pintype "unspecified"))
    )
    (net (code "165") (name "ROW1") (class "Default")
      (node (ref "ROW_MUX") (pin "9") (pinfunction "I0_9") (pintype "unspecified"))
      (node (ref "SW1") (pin "1") (pinfunction "1_1") (pintype "unspecified"))
      (node (ref "SW15") (pin "1") (pinfunction "1_1") (pintype "unspecified"))
      (node (ref "SW22") (pin "1") (pinfunction "1_1") (pintype "unspecified"))
      (node (ref "SW29") (pin "1") (pinfunction "1_1") (pintype "unspecified"))
      (node (ref "SW36") (pin "1") (pinfunction "1_1") (pintype "unspecified"))
      (node (ref "SW8") (pin "1") (pinfunction "1_1") (pintype "unspecified"))
    )
    (net (code "166") (name "ROW2") (class "Default")
      (node (ref "ROW_MUX") (pin "8") (pinfunction "I1_8") (pintype "unspecified"))
      (node (ref "SW16") (pin "1") (pinfunction "1_1") (pintype "unspecified"))
      (node (ref "SW2") (pin "1") (pinfunction "1_1") (pintype "unspecified"))
      (node (ref "SW23") (pin "1") (pinfunction "1_1") (pintype "unspecified"))
      (node (ref "SW30") (pin "1") (pinfunction "1_1") (pintype "unspecified"))
      (node (ref "SW37") (pin "1") (pinfunction "1_1") (pintype "unspecified"))
      (node (ref "SW9") (pin "1") (pinfunction "1_1") (pintype "unspecified"))
    )
    (net (code "167") (name "ROW3") (class "Default")
      (node (ref "ROW_MUX") (pin "7") (pinfunction "I2_7") (pintype "unspecified"))
      (node (ref "SW10") (pin "1") (pinfunction "1_1") (pintype "unspecified"))
      (node (ref "SW17") (pin "1") (pinfunction "1_1") (pintype "unspecified"))
      (node (ref "SW24") (pin "1") (pinfunction "1_1") (pintype "unspecified"))
      (node (ref "SW3") (pin "1") (pinfunction "1_1") (pintype "unspecified"))
      (node (ref "SW31") (pin "1") (pinfunction "1_1") (pintype "unspecified"))
      (node (ref "SW38") (pin "1") (pinfunction "1_1") (pintype "unspecified"))
    )
    (net (code "168") (name "ROW4") (class "Default")
      (node (ref "ROW_MUX") (pin "6") (pinfunction "I3_6") (pintype "unspecified"))
      (node (ref "SW11") (pin "1") (pinfunction "1_1") (pintype "unspecified"))
      (node (ref "SW18") (pin "1") (pinfunction "1_1") (pintype "unspecified"))
      (node (ref "SW25") (pin "1") (pinfunction "1_1") (pintype "unspecified"))
      (node (ref "SW32") (pin "1") (pinfunction "1_1") (pintype "unspecified"))
      (node (ref "SW39") (pin "1") (pinfunction "1_1") (pintype "unspecified"))
      (node (ref "SW4") (pin "1") (pinfunction "1_1") (pintype "unspecified"))
    )
    (net (code "169") (name "ROW5") (class "Default")
      (node (ref "ROW_MUX") (pin "4") (pinfunction "I5_4") (pintype "unspecified"))
      (node (ref "ROW_MUX") (pin "5") (pinfunction "I4_5") (pintype "unspecified"))
      (node (ref "SW12") (pin "1") (pinfunction "1_1") (pintype "unspecified"))
      (node (ref "SW19") (pin "1") (pinfunction "1_1") (pintype "unspecified"))
      (node (ref "SW26") (pin "1") (pinfunction "1_1") (pintype "unspecified"))
      (node (ref "SW33") (pin "1") (pinfunction "1_1") (pintype "unspecified"))
      (node (ref "SW40") (pin "1") (pinfunction "1_1") (pintype "unspecified"))
      (node (ref "SW5") (pin "1") (pinfunction "1_1") (pintype "unspecified"))
    )
    (net (code "170") (name "ROW6") (class "Default")
      (node (ref "ROW_MUX") (pin "3") (pinfunction "I6_3") (pintype "unspecified"))
      (node (ref "SW13") (pin "1") (pinfunction "1_1") (pintype "unspecified"))
      (node (ref "SW20") (pin "1") (pinfunction "1_1") (pintype "unspecified"))
      (node (ref "SW27") (pin "1") (pinfunction "1_1") (pintype "unspecified"))
      (node (ref "SW34") (pin "1") (pinfunction "1_1") (pintype "unspecified"))
      (node (ref "SW41") (pin "1") (pinfunction "1_1") (pintype "unspecified"))
      (node (ref "SW6") (pin "1") (pinfunction "1_1") (pintype "unspecified"))
    )
    (net (code "171") (name "ROW7") (class "Default")
      (node (ref "ROW_MUX") (pin "2") (pinfunction "I7_2") (pintype "unspecified"))
      (node (ref "SW14") (pin "1") (pinfunction "1_1") (pintype "unspecified"))
      (node (ref "SW21") (pin "1") (pinfunction "1_1") (pintype "unspecified"))
      (node (ref "SW28") (pin "1") (pinfunction "1_1") (pintype "unspecified"))
      (node (ref "SW35") (pin "1") (pinfunction "1_1") (pintype "unspecified"))
      (node (ref "SW42") (pin "1") (pinfunction "1_1") (pintype "unspecified"))
      (node (ref "SW7") (pin "1") (pinfunction "1_1") (pintype "unspecified"))
    )
    (net (code "172") (name "SCL") (class "Default")
      (node (ref "R68") (pin "1") (pinfunction "~_1") (pintype "unspecified"))
      (node (ref "R69") (pin "2") (pinfunction "~_2") (pintype "unspecified"))
      (node (ref "Screen") (pin "3") (pinfunction "Pin_3_3") (pintype "unspecified"))
      (node (ref "U1") (pin "19") (pinfunction "19_19") (pintype "bidirectional"))
    )
    (net (code "173") (name "SDA") (class "Default")
      (node (ref "R68") (pin "2") (pinfunction "~_2") (pintype "unspecified"))
      (node (ref "Screen") (pin "4") (pinfunction "Pin_4_4") (pintype "unspecified"))
      (node (ref "U1") (pin "18") (pinfunction "18_18") (pintype "bidirectional"))
    )
    (net (code "174") (name "TPWR") (class "Default")
      (node (ref "SW49") (pin "2") (pinfunction "2_2") (pintype "unspecified"))
      (node (ref "U1") (pin "VIN") (pinfunction "VIN_VIN") (pintype "unspecified"))
    )
    (net (code "175") (name "VIN_FUSED") (class "Default")
      (node (ref "C5") (pin "2") (pinfunction "2_2") (pintype "input"))
      (node (ref "C6") (pin "2") (pinfunction "2_2") (pintype "unspecified"))
      (node (ref "D44") (pin "1") (pinfunction "K_1") (pintype "input"))
      (node (ref "F1") (pin "2") (pinfunction "2_2") (pintype "unspecified"))
      (node (ref "SW49") (pin "4") (pinfunction "4_4") (pintype "unspecified"))
      (node (ref "SW49") (pin "6") (pinfunction "6_6") (pintype "unspecified"))
      (node (ref "U6") (pin "1") (pinfunction "1_1") (pintype "unspecified"))
    )
    (net (code "176") (name "VIN_RAW") (class "Default")
      (node (ref "F1") (pin "1") (pinfunction "1_1") (pintype "unspecified"))
      (node (ref "J1") (pin "1") (pinfunction "1_1") (pintype "unspecified"))
    )
    (net (code "177") (name "VLED") (class "Default")
      (node (ref "C2") (pin "1") (pinfunction "~_1") (pintype "unspecified"))
      (node (ref "C7") (pin "2") (pinfunction "2_2") (pintype "unspecified"))
      (node (ref "D1") (pin "1") (pinfunction "VDD_1") (pintype "unspecified"))
      (node (ref "U6") (pin "2") (pinfunction "2_2") (pintype "unspecified"))
    )
    (net (code "178") (name "VREF") (class "Default")
      (node (ref "R46") (pin "2") (pinfunction "~_2") (pintype "unspecified"))
      (node (ref "R47") (pin "2") (pinfunction "~_2") (pintype "unspecified"))
      (node (ref "U15") (pin "3") (pinfunction "INA+_3") (pintype "unspecified"))
      (node (ref "U16") (pin "3") (pinfunction "INA+_3") (pintype "unspecified"))
      (node (ref "U17") (pin "3") (pinfunction "INA+_3") (pintype "unspecified"))
      (node (ref "U18") (pin "3") (pinfunction "INA+_3") (pintype "unspecified"))
      (node (ref "U19") (pin "3") (pinfunction "INA+_3") (pintype "unspecified"))
      (node (ref "U20") (pin "3") (pinfunction "INA+_3") (pintype "unspecified"))
    )
    (net (code "179") (name "unconnected-(D42-DOUT-Pad2)") (class "Default")
      (node (ref "D42") (pin "2") (pinfunction "DOUT_2") (pintype "output+no_connect"))
    )
    (net (code "180") (name "unconnected-(J2-Pad1)") (class "Default")
      (node (ref "J2") (pin "1") (pinfunction "1_1") (pintype "unspecified+no_connect"))
    )
    (net (code "181") (name "unconnected-(J2-Pad3)") (class "Default")
      (node (ref "J2") (pin "3") (pinfunction "3_3") (pintype "unspecified+no_connect"))
    )
    (net (code "182") (name "unconnected-(J2-Pad6)") (class "Default")
      (node (ref "J2") (pin "6") (pinfunction "6_6") (pintype "unspecified+no_connect"))
    )
    (net (code "183") (name "unconnected-(J2-Pad7)") (class "Default")
      (node (ref "J2") (pin "7") (pinfunction "7_7") (pintype "unspecified+no_connect"))
    )
    (net (code "184") (name "unconnected-(J3-Pad1)") (class "Default")
      (node (ref "J3") (pin "1") (pinfunction "1_1") (pintype "unspecified+no_connect"))
    )
    (net (code "185") (name "unconnected-(J3-Pad3)") (class "Default")
      (node (ref "J3") (pin "3") (pinfunction "3_3") (pintype "unspecified+no_connect"))
    )
    (net (code "186") (name "unconnected-(J3-Pad6)") (class "Default")
      (node (ref "J3") (pin "6") (pinfunction "6_6") (pintype "unspecified+no_connect"))
    )
    (net (code "187") (name "unconnected-(J3-Pad7)") (class "Default")
      (node (ref "J3") (pin "7") (pinfunction "7_7") (pintype "unspecified+no_connect"))
    )
    (net (code "188") (name "unconnected-(U1-ON{slash}OFF-PadON-OFF)") (class "Default")
      (node (ref "U1") (pin "ON-OFF") (pinfunction "ON/OFF_ON-OFF") (pintype "bidirectional+no_connect"))
    )
    (net (code "189") (name "unconnected-(U1-PROGRAM-PadPGM)") (class "Default")
      (node (ref "U1") (pin "PGM") (pinfunction "PROGRAM_PGM") (pintype "bidirectional+no_connect"))
    )
    (net (code "190") (name "unconnected-(U1-Pad12)") (class "Default")
      (node (ref "U1") (pin "12") (pinfunction "12_12") (pintype "bidirectional+no_connect"))
    )
    (net (code "191") (name "unconnected-(U1-Pad13)") (class "Default")
      (node (ref "U1") (pin "13") (pinfunction "13_13") (pintype "bidirectional+no_connect"))
    )
    (net (code "192") (name "unconnected-(U1-Pad23)") (class "Default")
      (node (ref "U1") (pin "23") (pinfunction "23_23") (pintype "bidirectional+no_connect"))
    )
    (net (code "193") (name "unconnected-(U1-PadVBAT)") (class "Default")
      (node (ref "U1") (pin "VBAT") (pinfunction "VBAT_VBAT") (pintype "unspecified+no_connect"))
    )
    (net (code "194") (name "unconnected-(U5-NC-Pad1)") (class "Default")
      (node (ref "U5") (pin "1") (pinfunction "NC_1") (pintype "unspecified+no_connect"))
    )
    (net (code "195") (name "unconnected-(U5-NC-Pad4)") (class "Default")
      (node (ref "U5") (pin "4") (pinfunction "NC_4") (pintype "unspecified+no_connect"))
    )
  )
)
